# 000018_PGKB_Rev_2_00.net
KiCad netlist of a schematic drawn in EAGLE
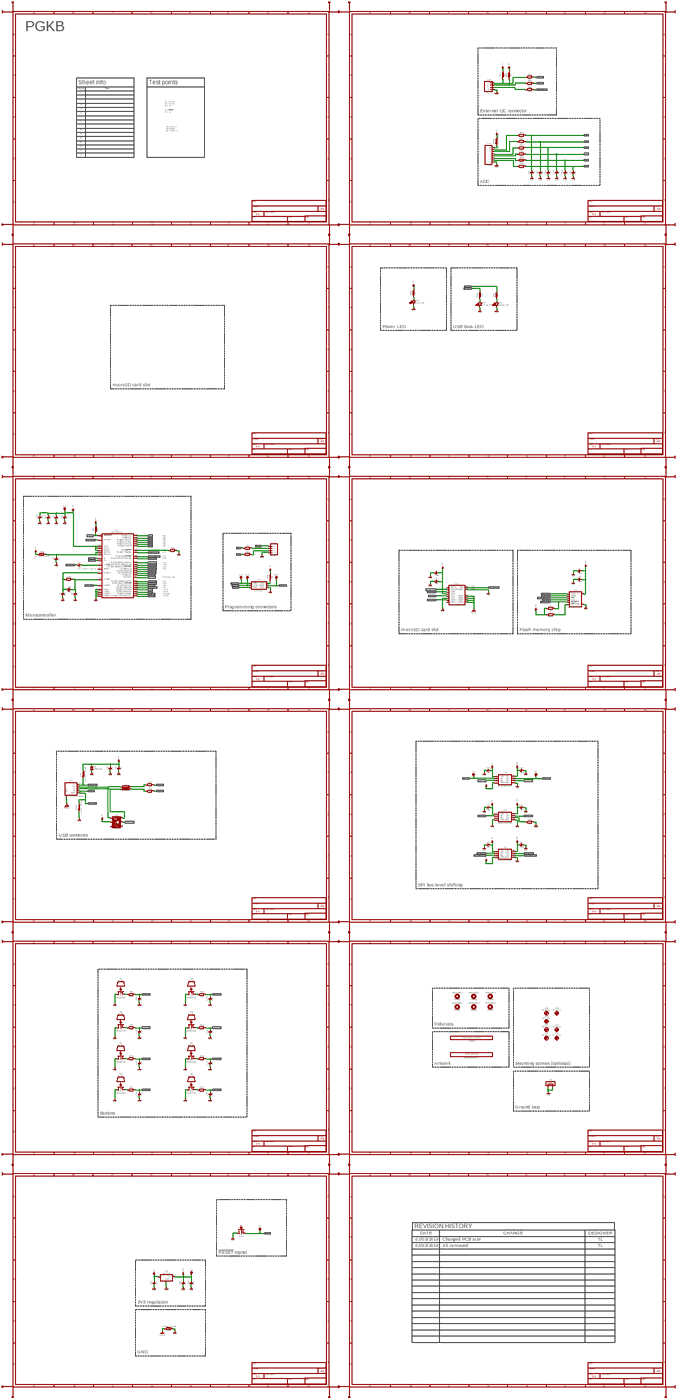
[diagram p0: schematic, sheet 1, overview]
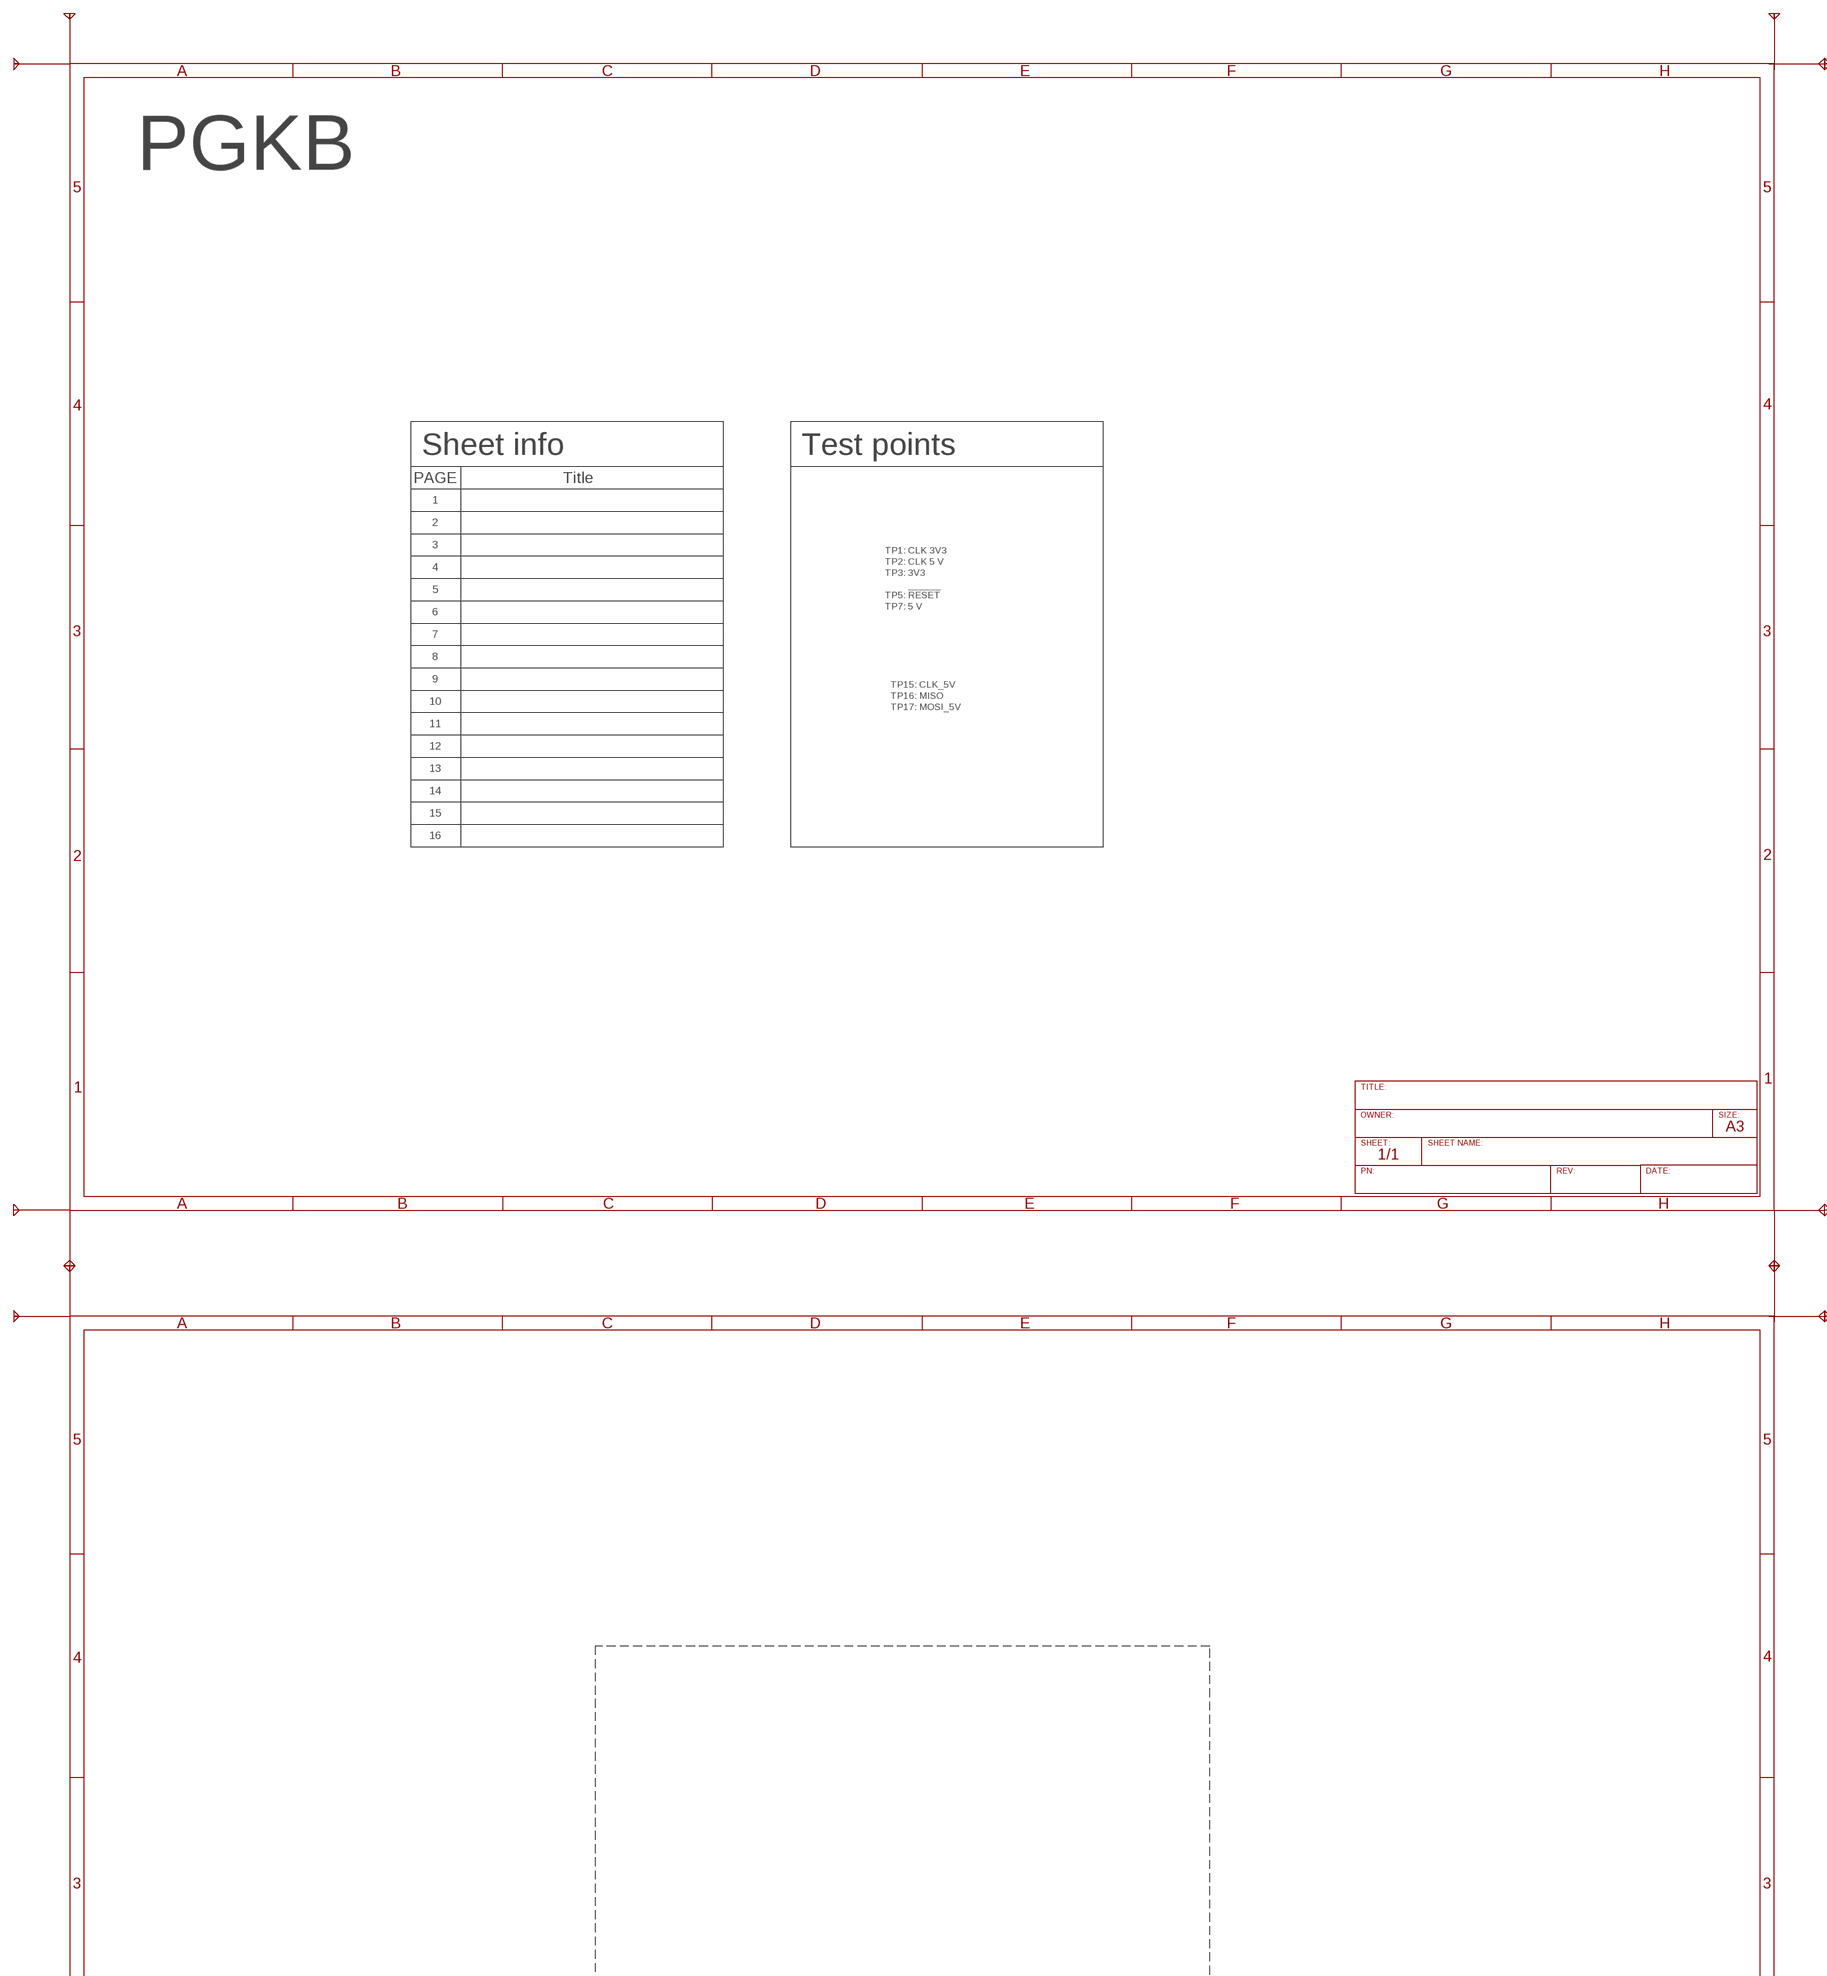
[diagram p1: schematic, sheet 1, part 1 of 8]
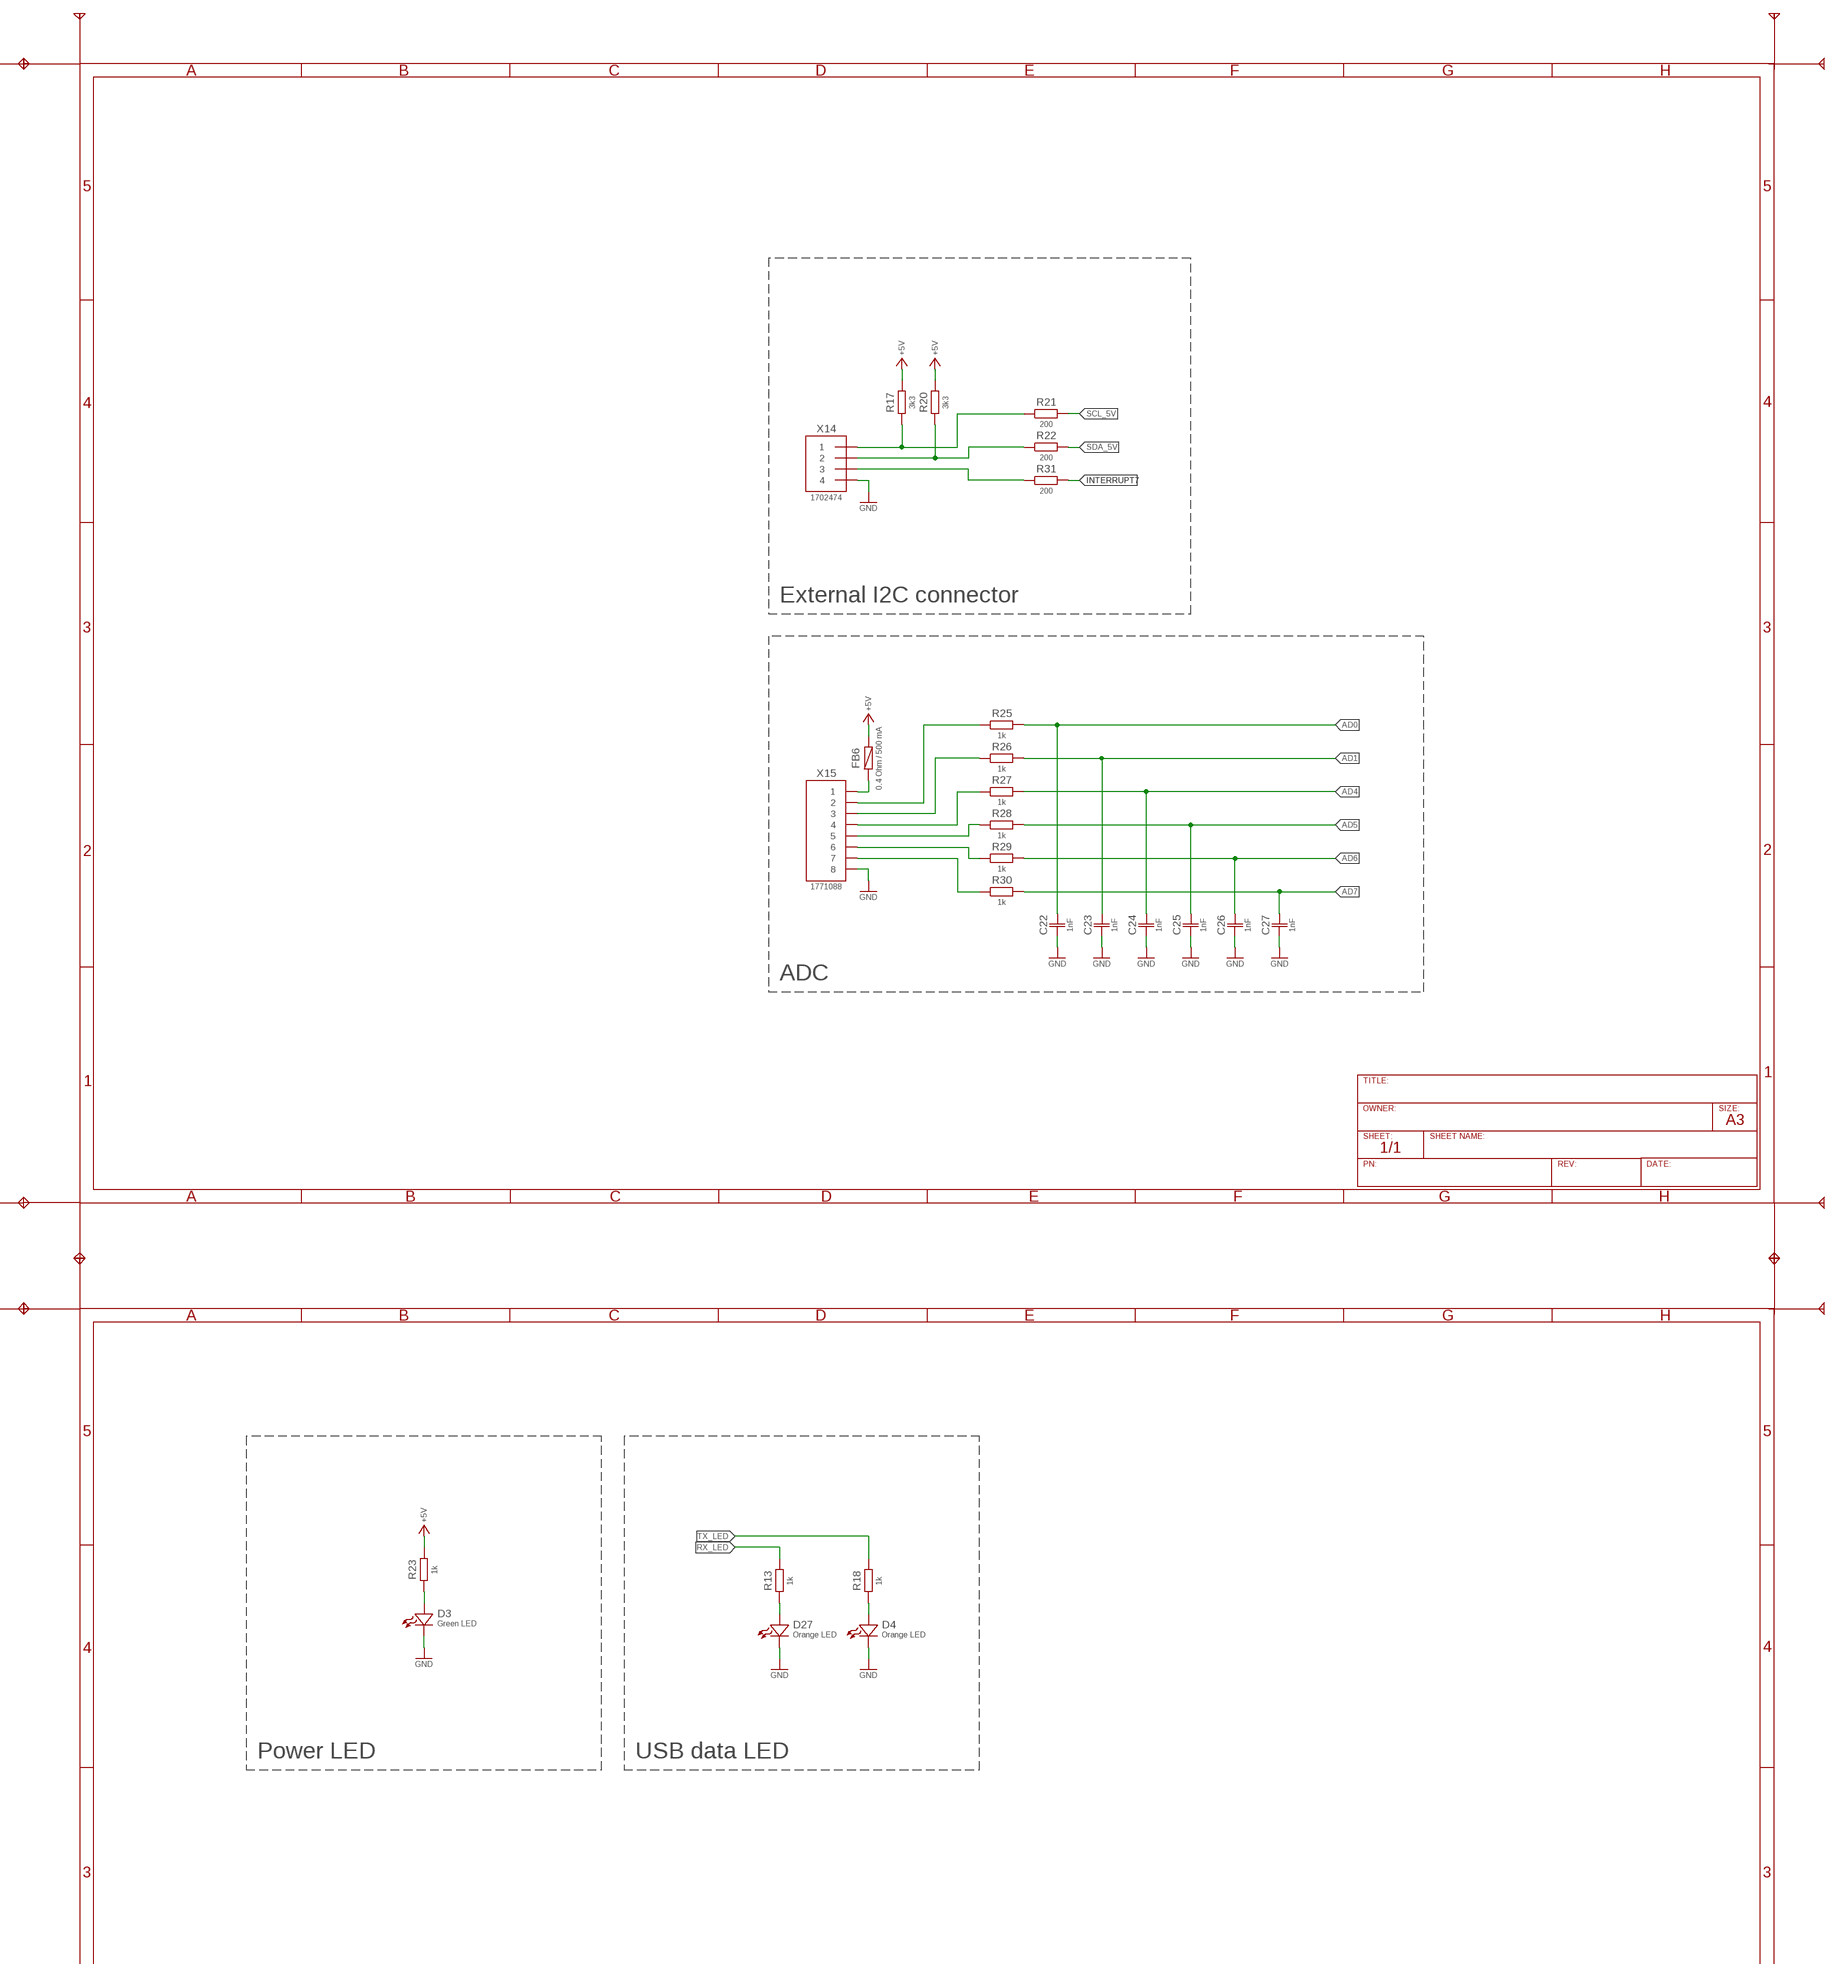
[diagram p2: schematic, sheet 1, part 2 of 8]
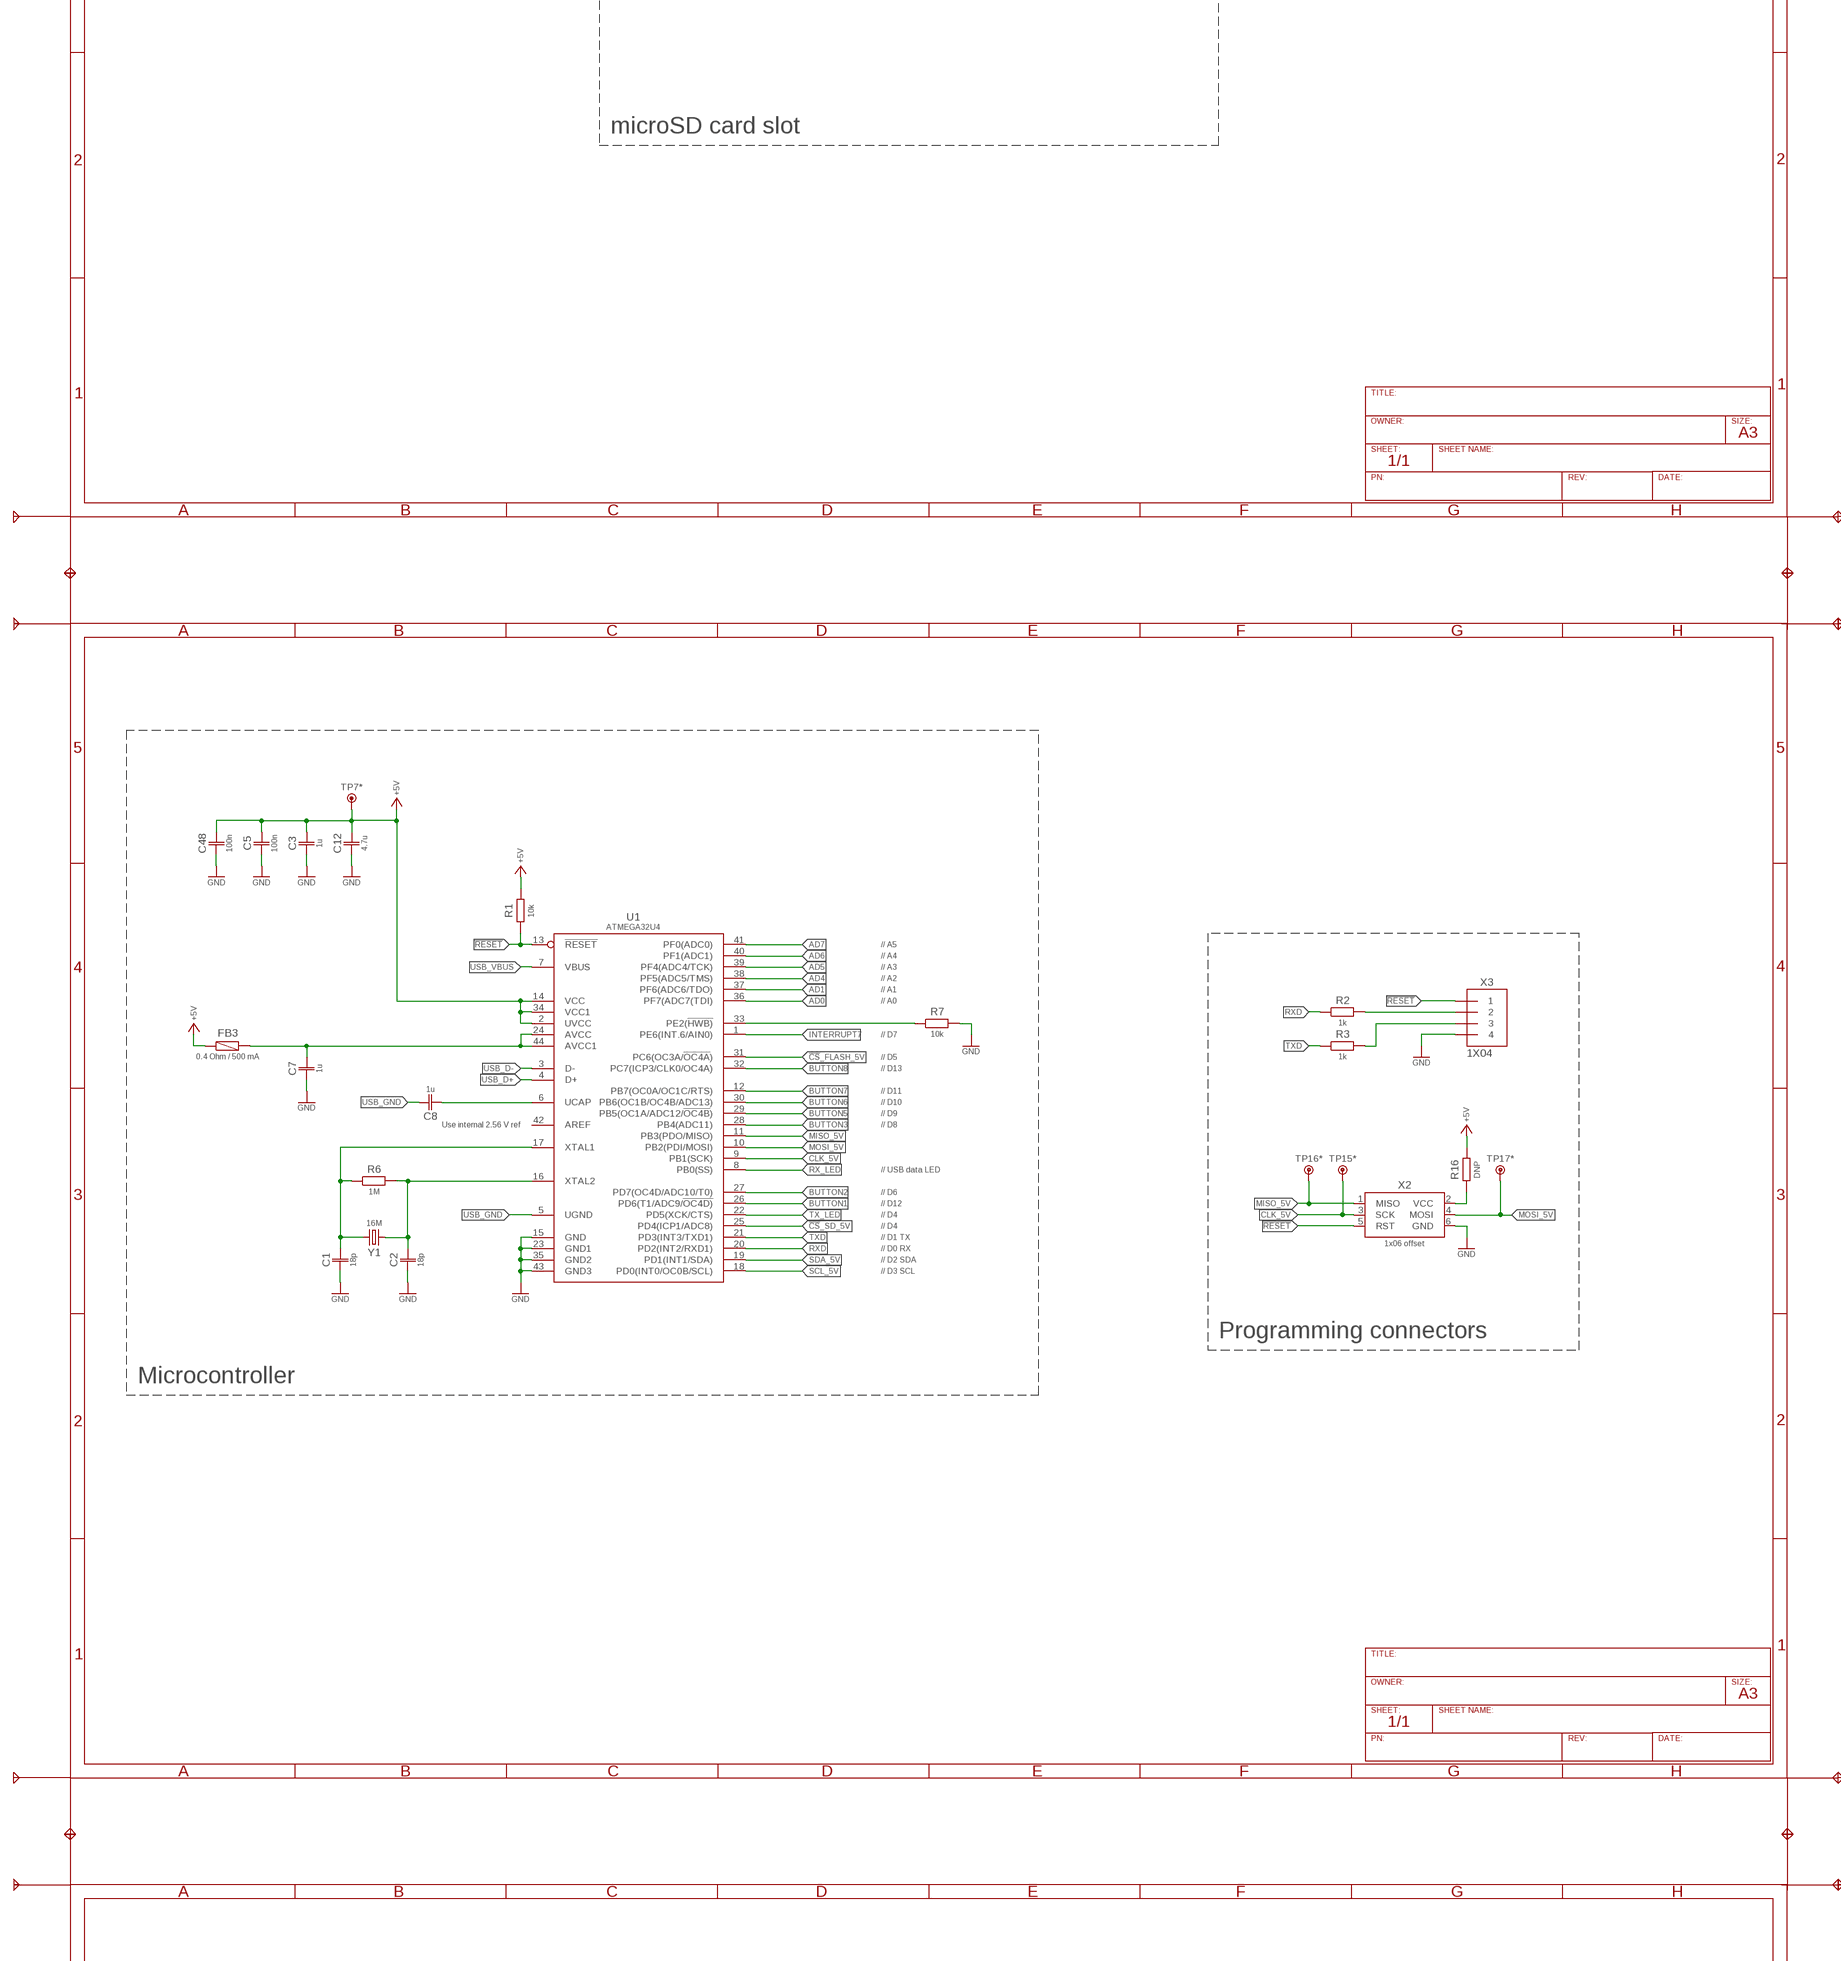
[diagram p3: schematic, sheet 1, part 3 of 8]
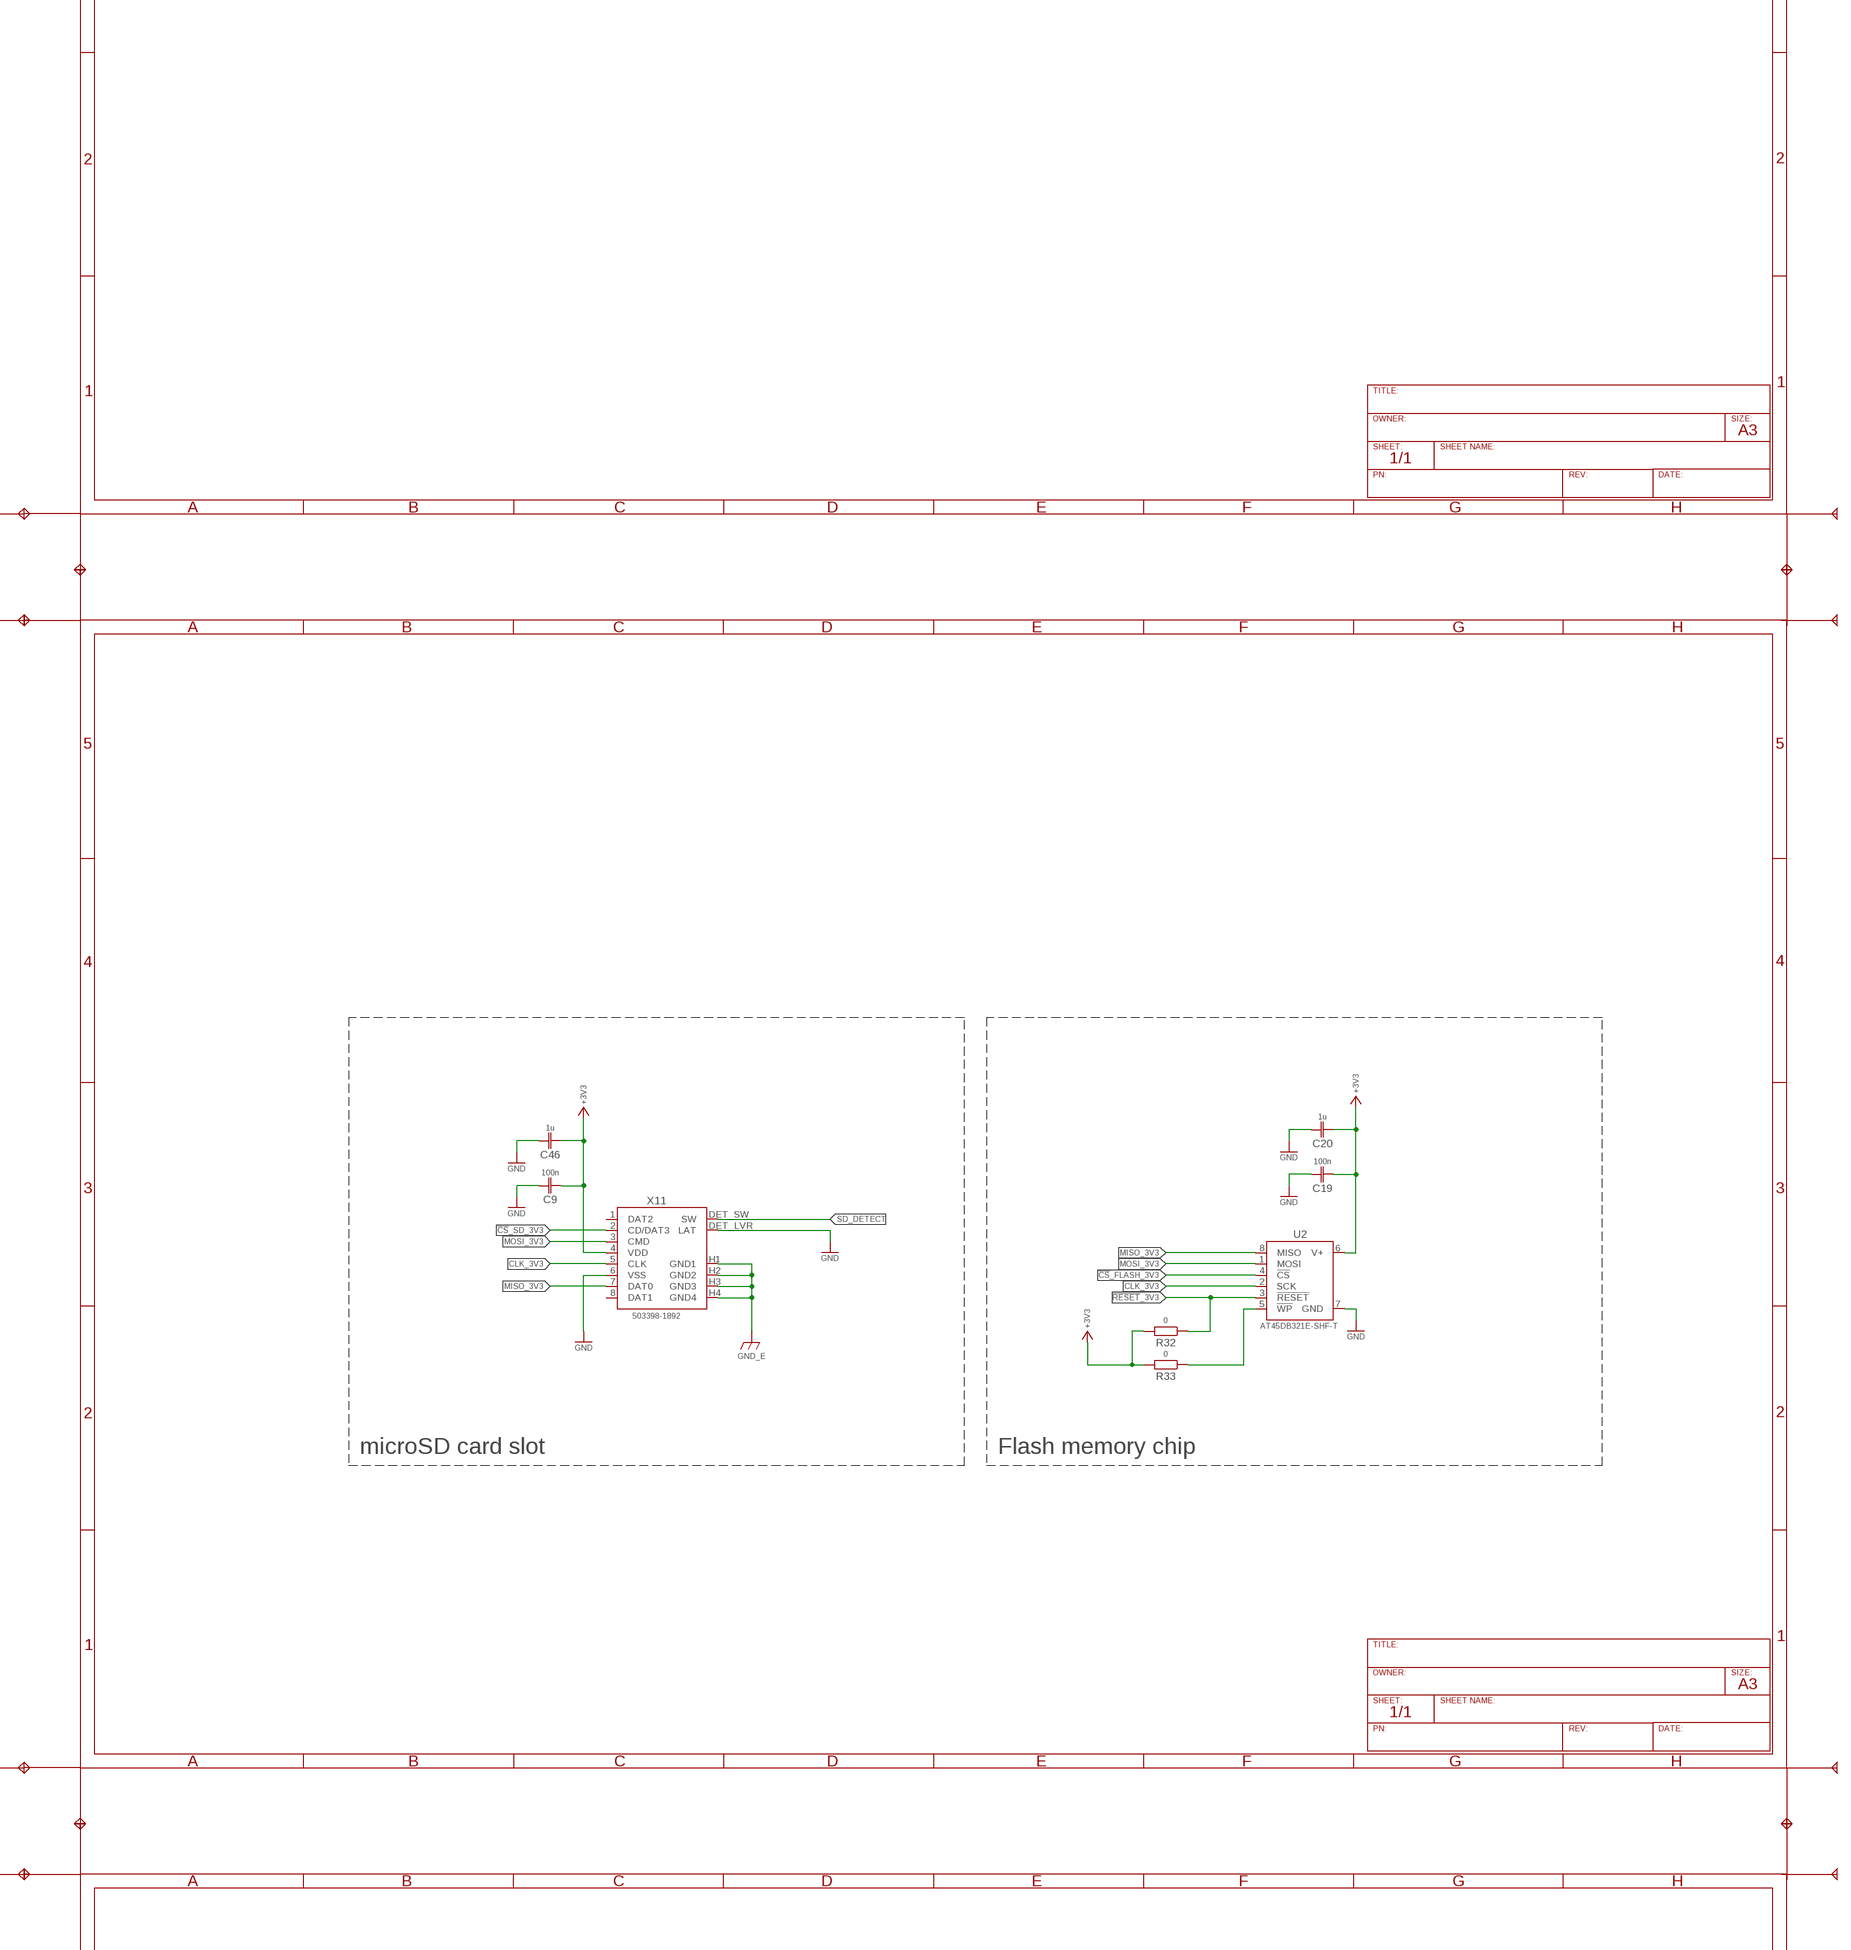
[diagram p4: schematic, sheet 1, part 4 of 8]
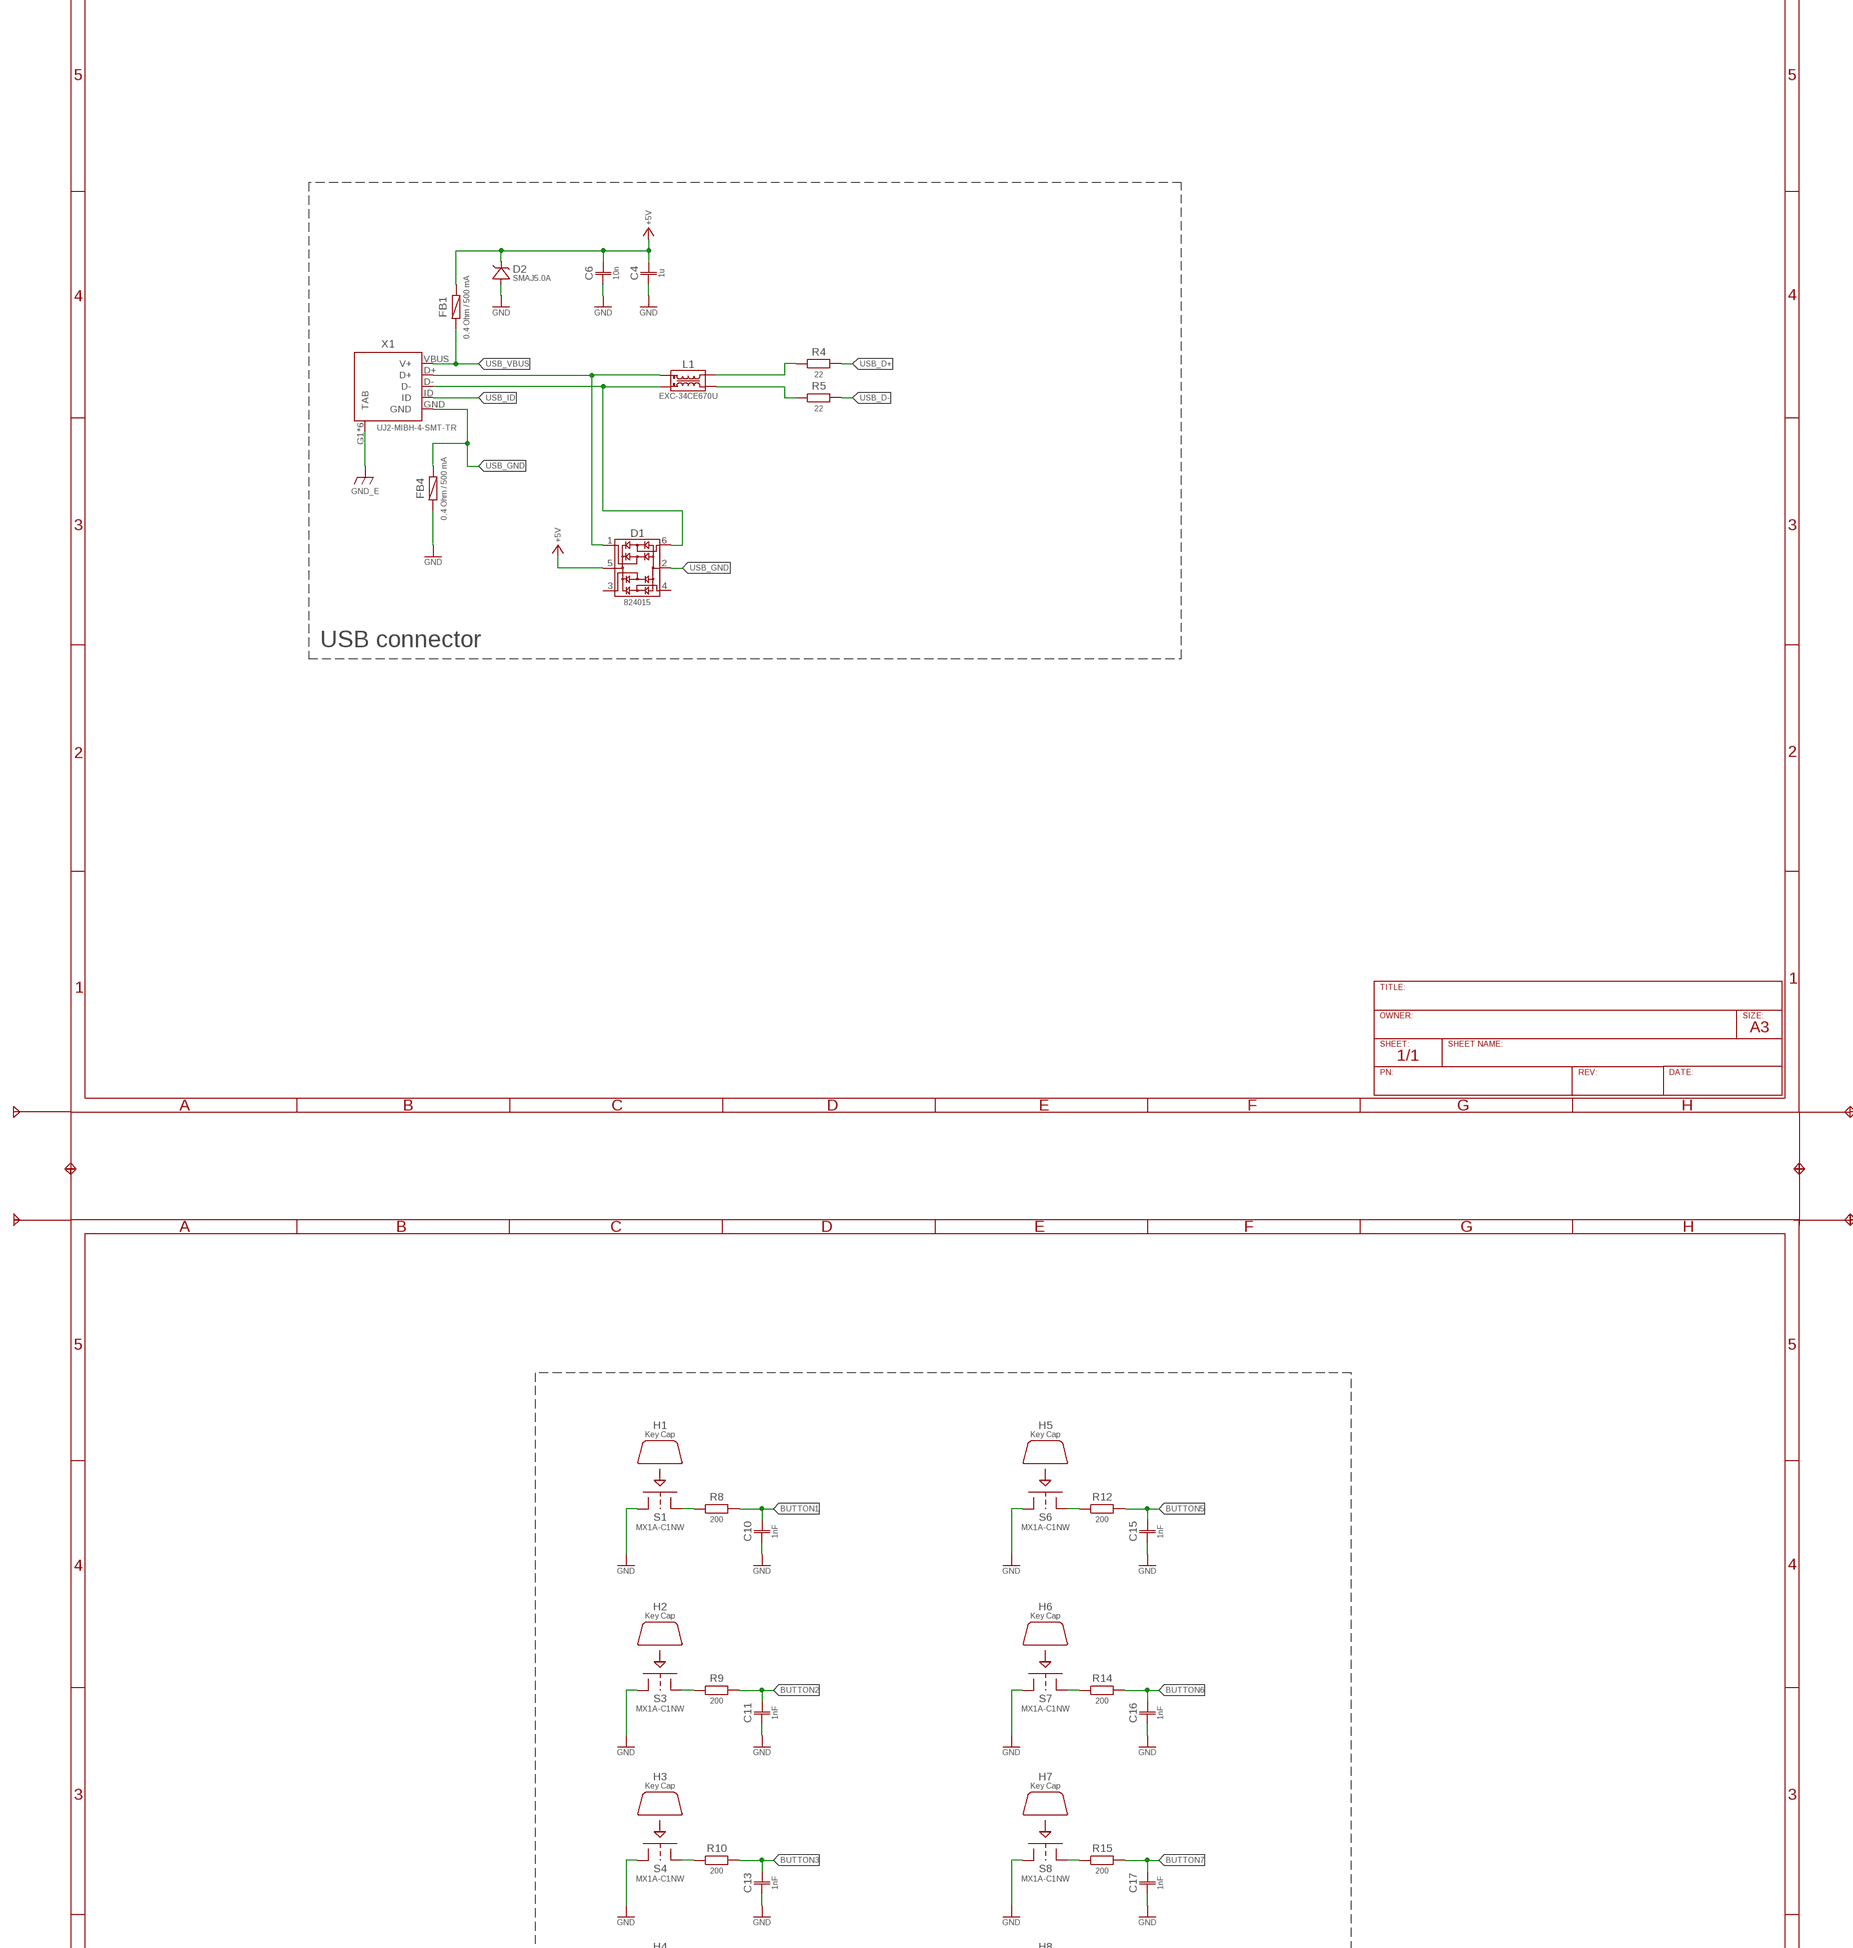
[diagram p5: schematic, sheet 1, part 5 of 8]
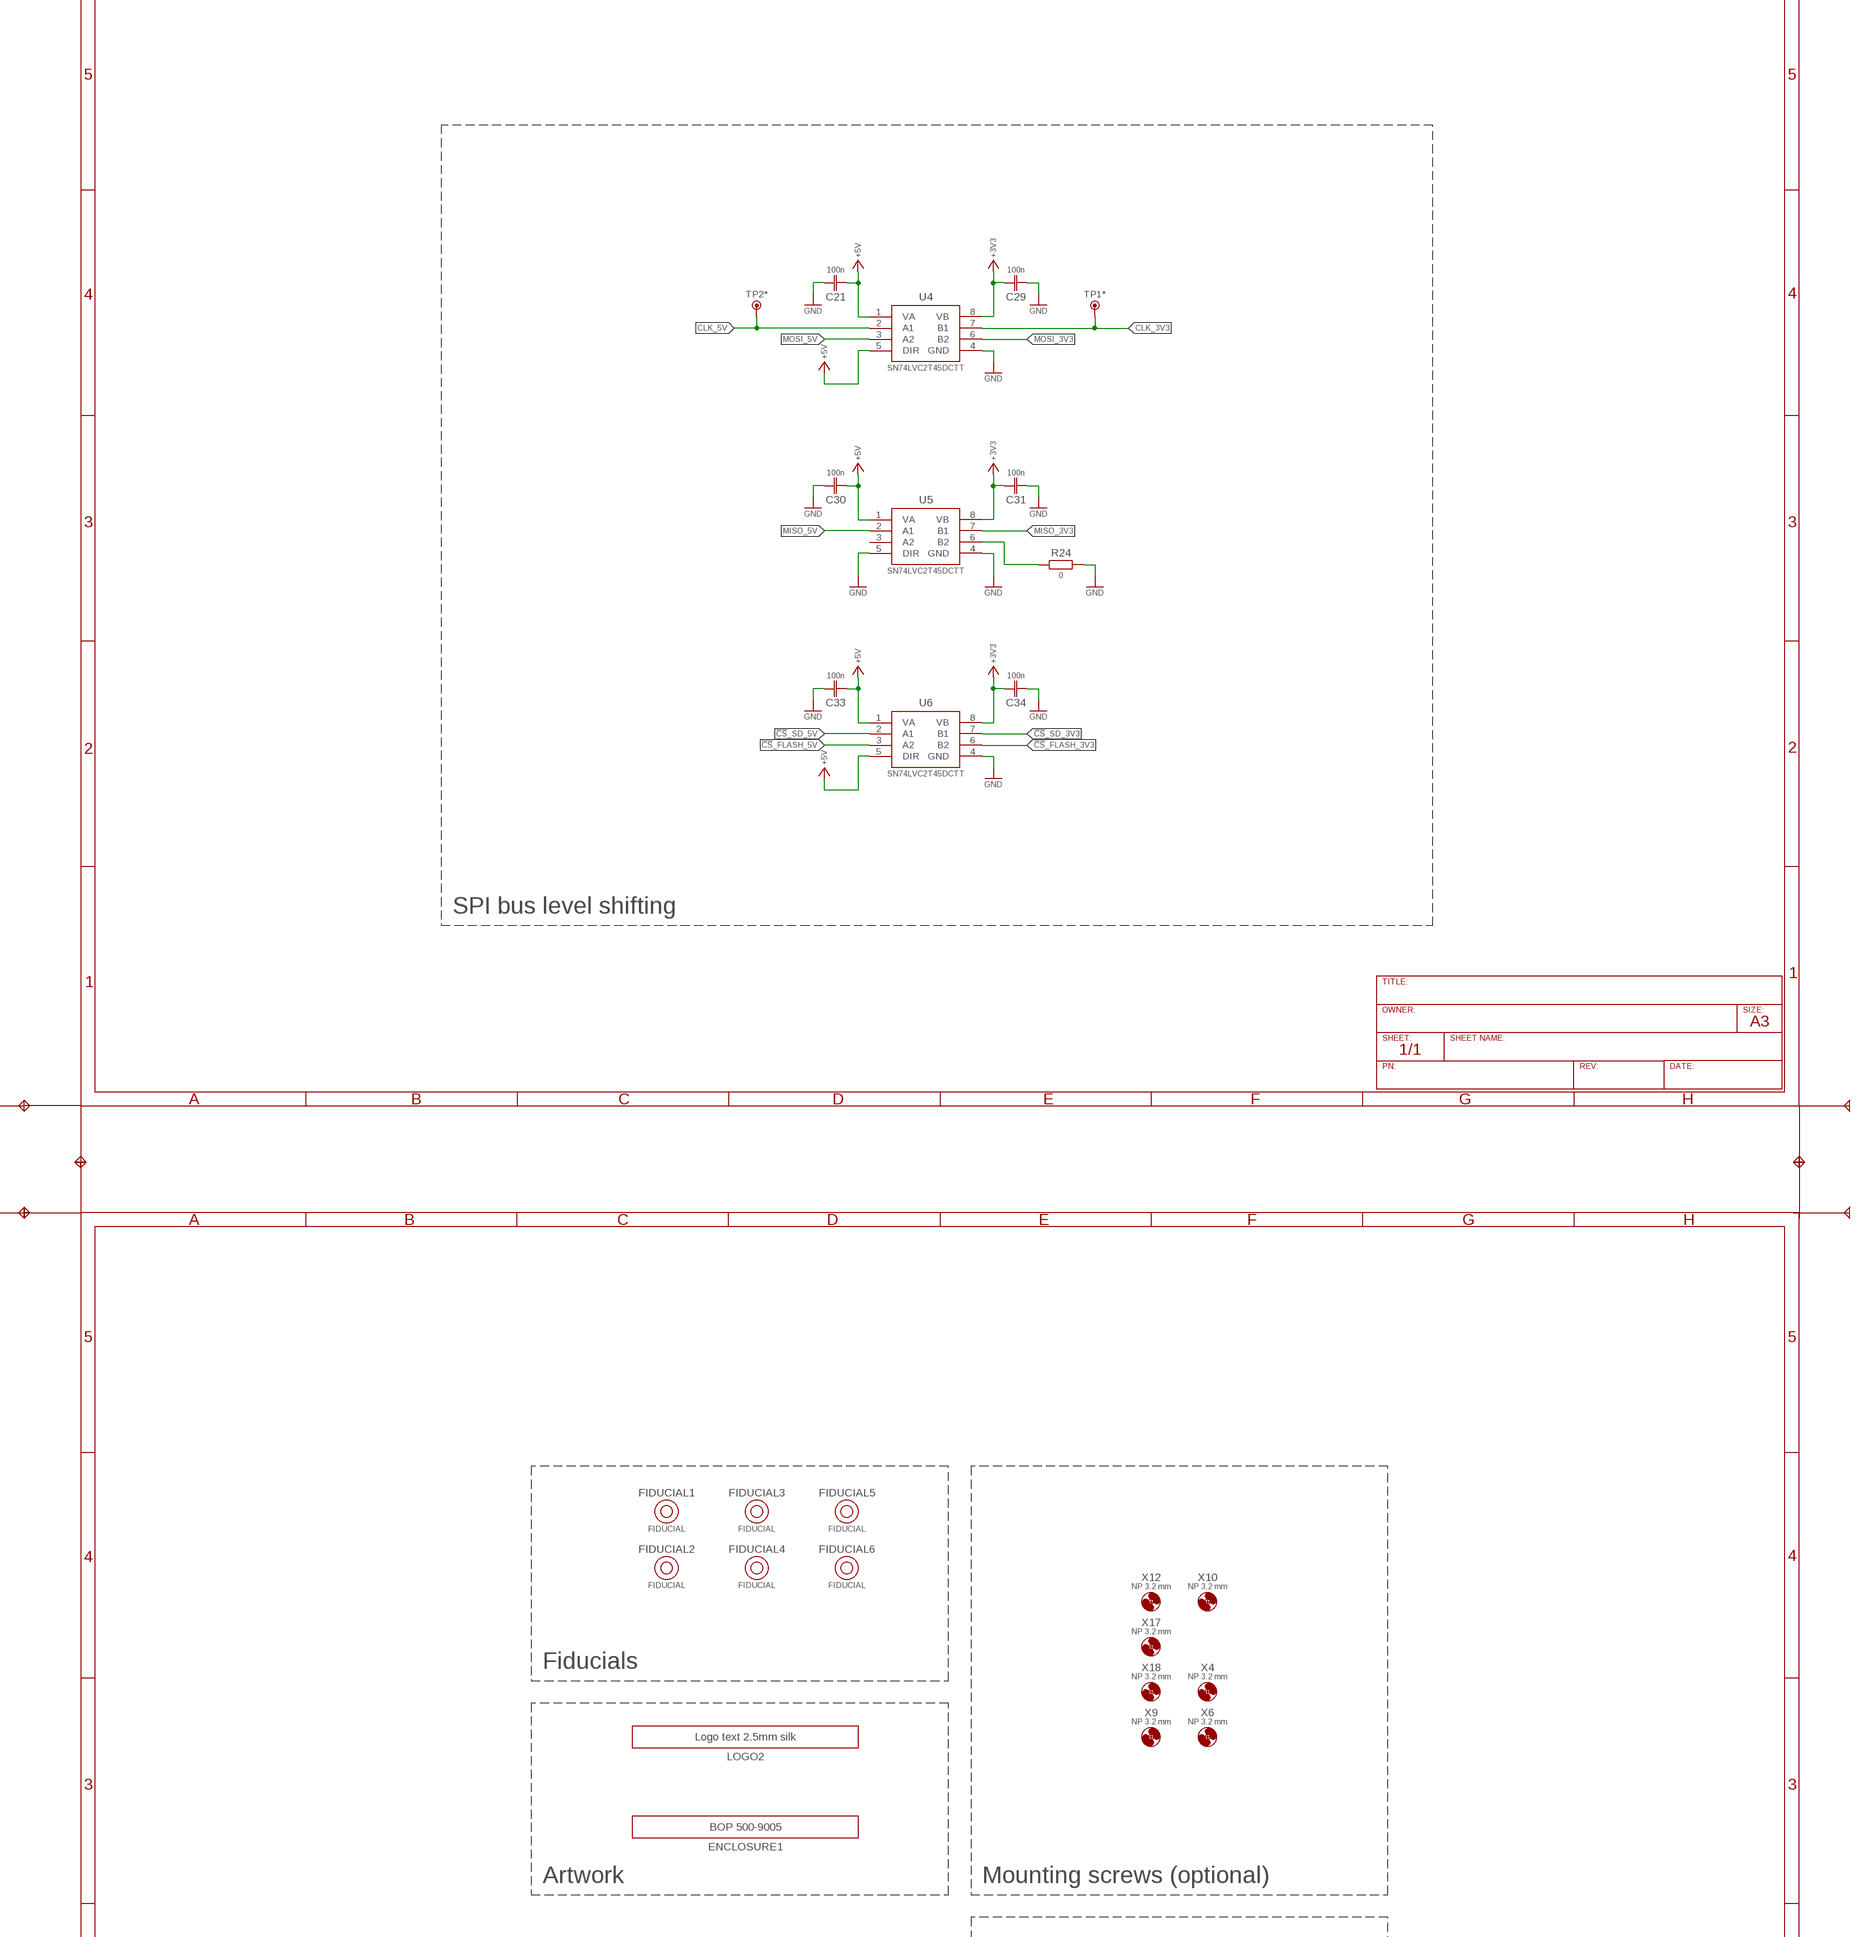
[diagram p6: schematic, sheet 1, part 6 of 8]
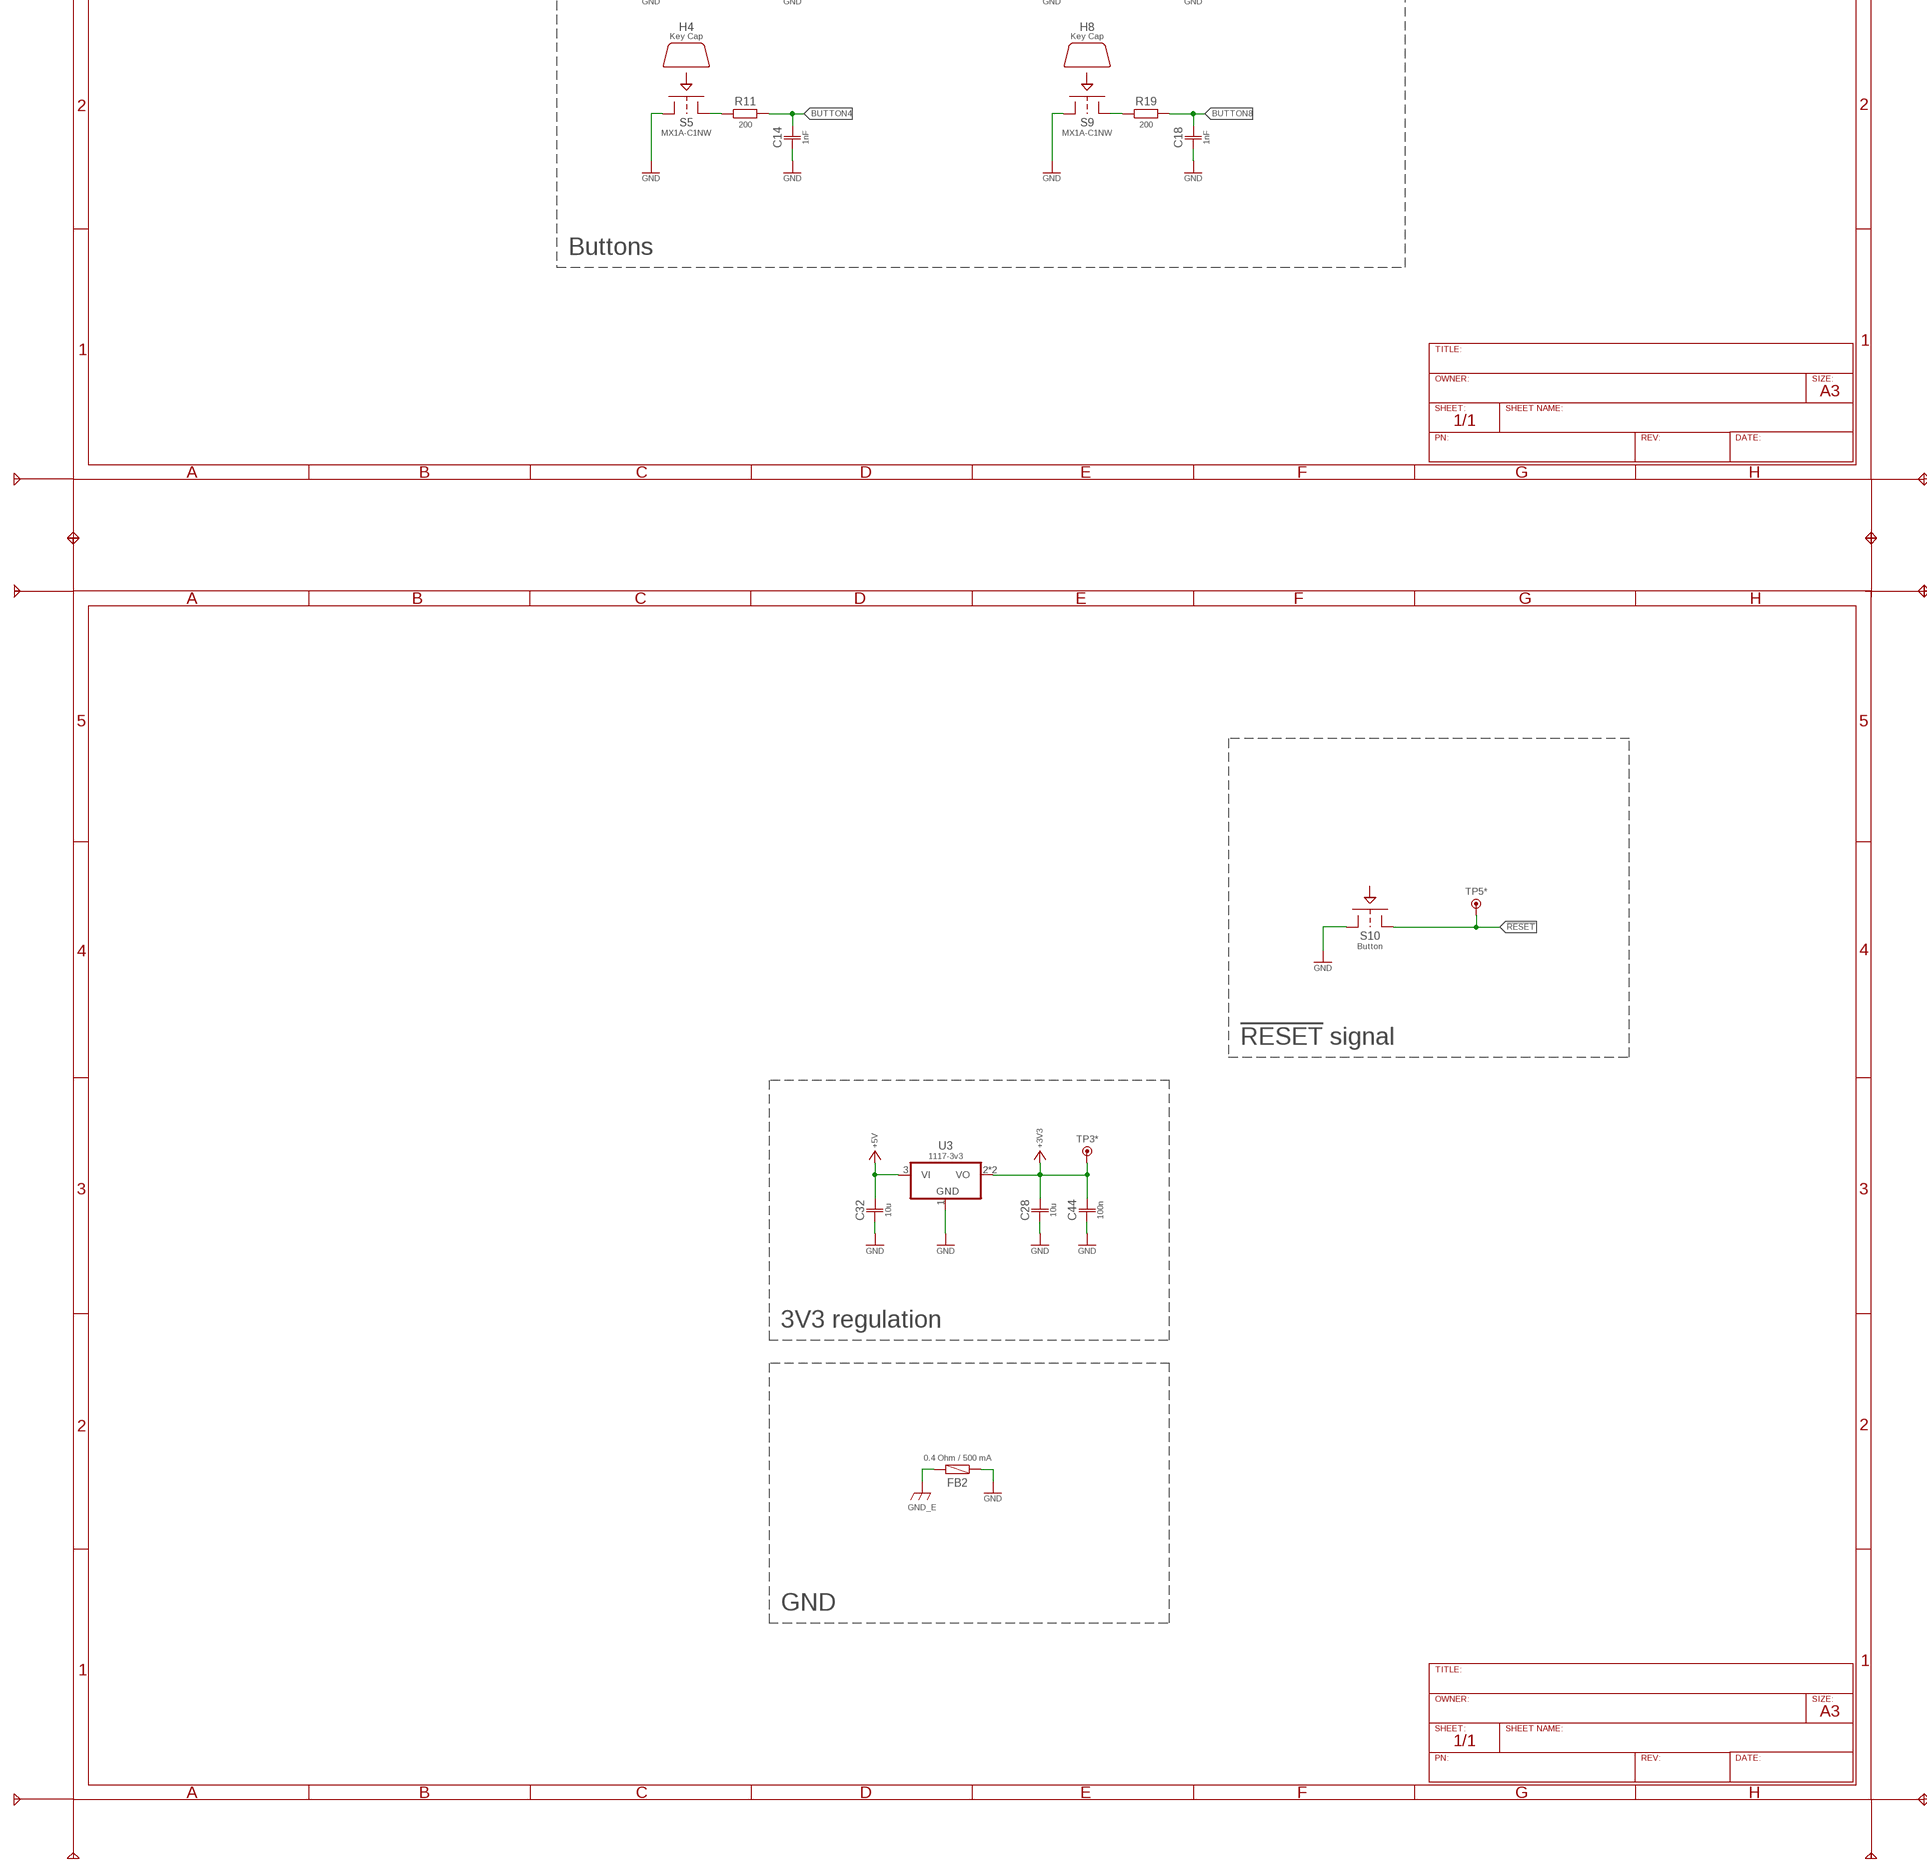
[diagram p7: schematic, sheet 1, part 7 of 8]
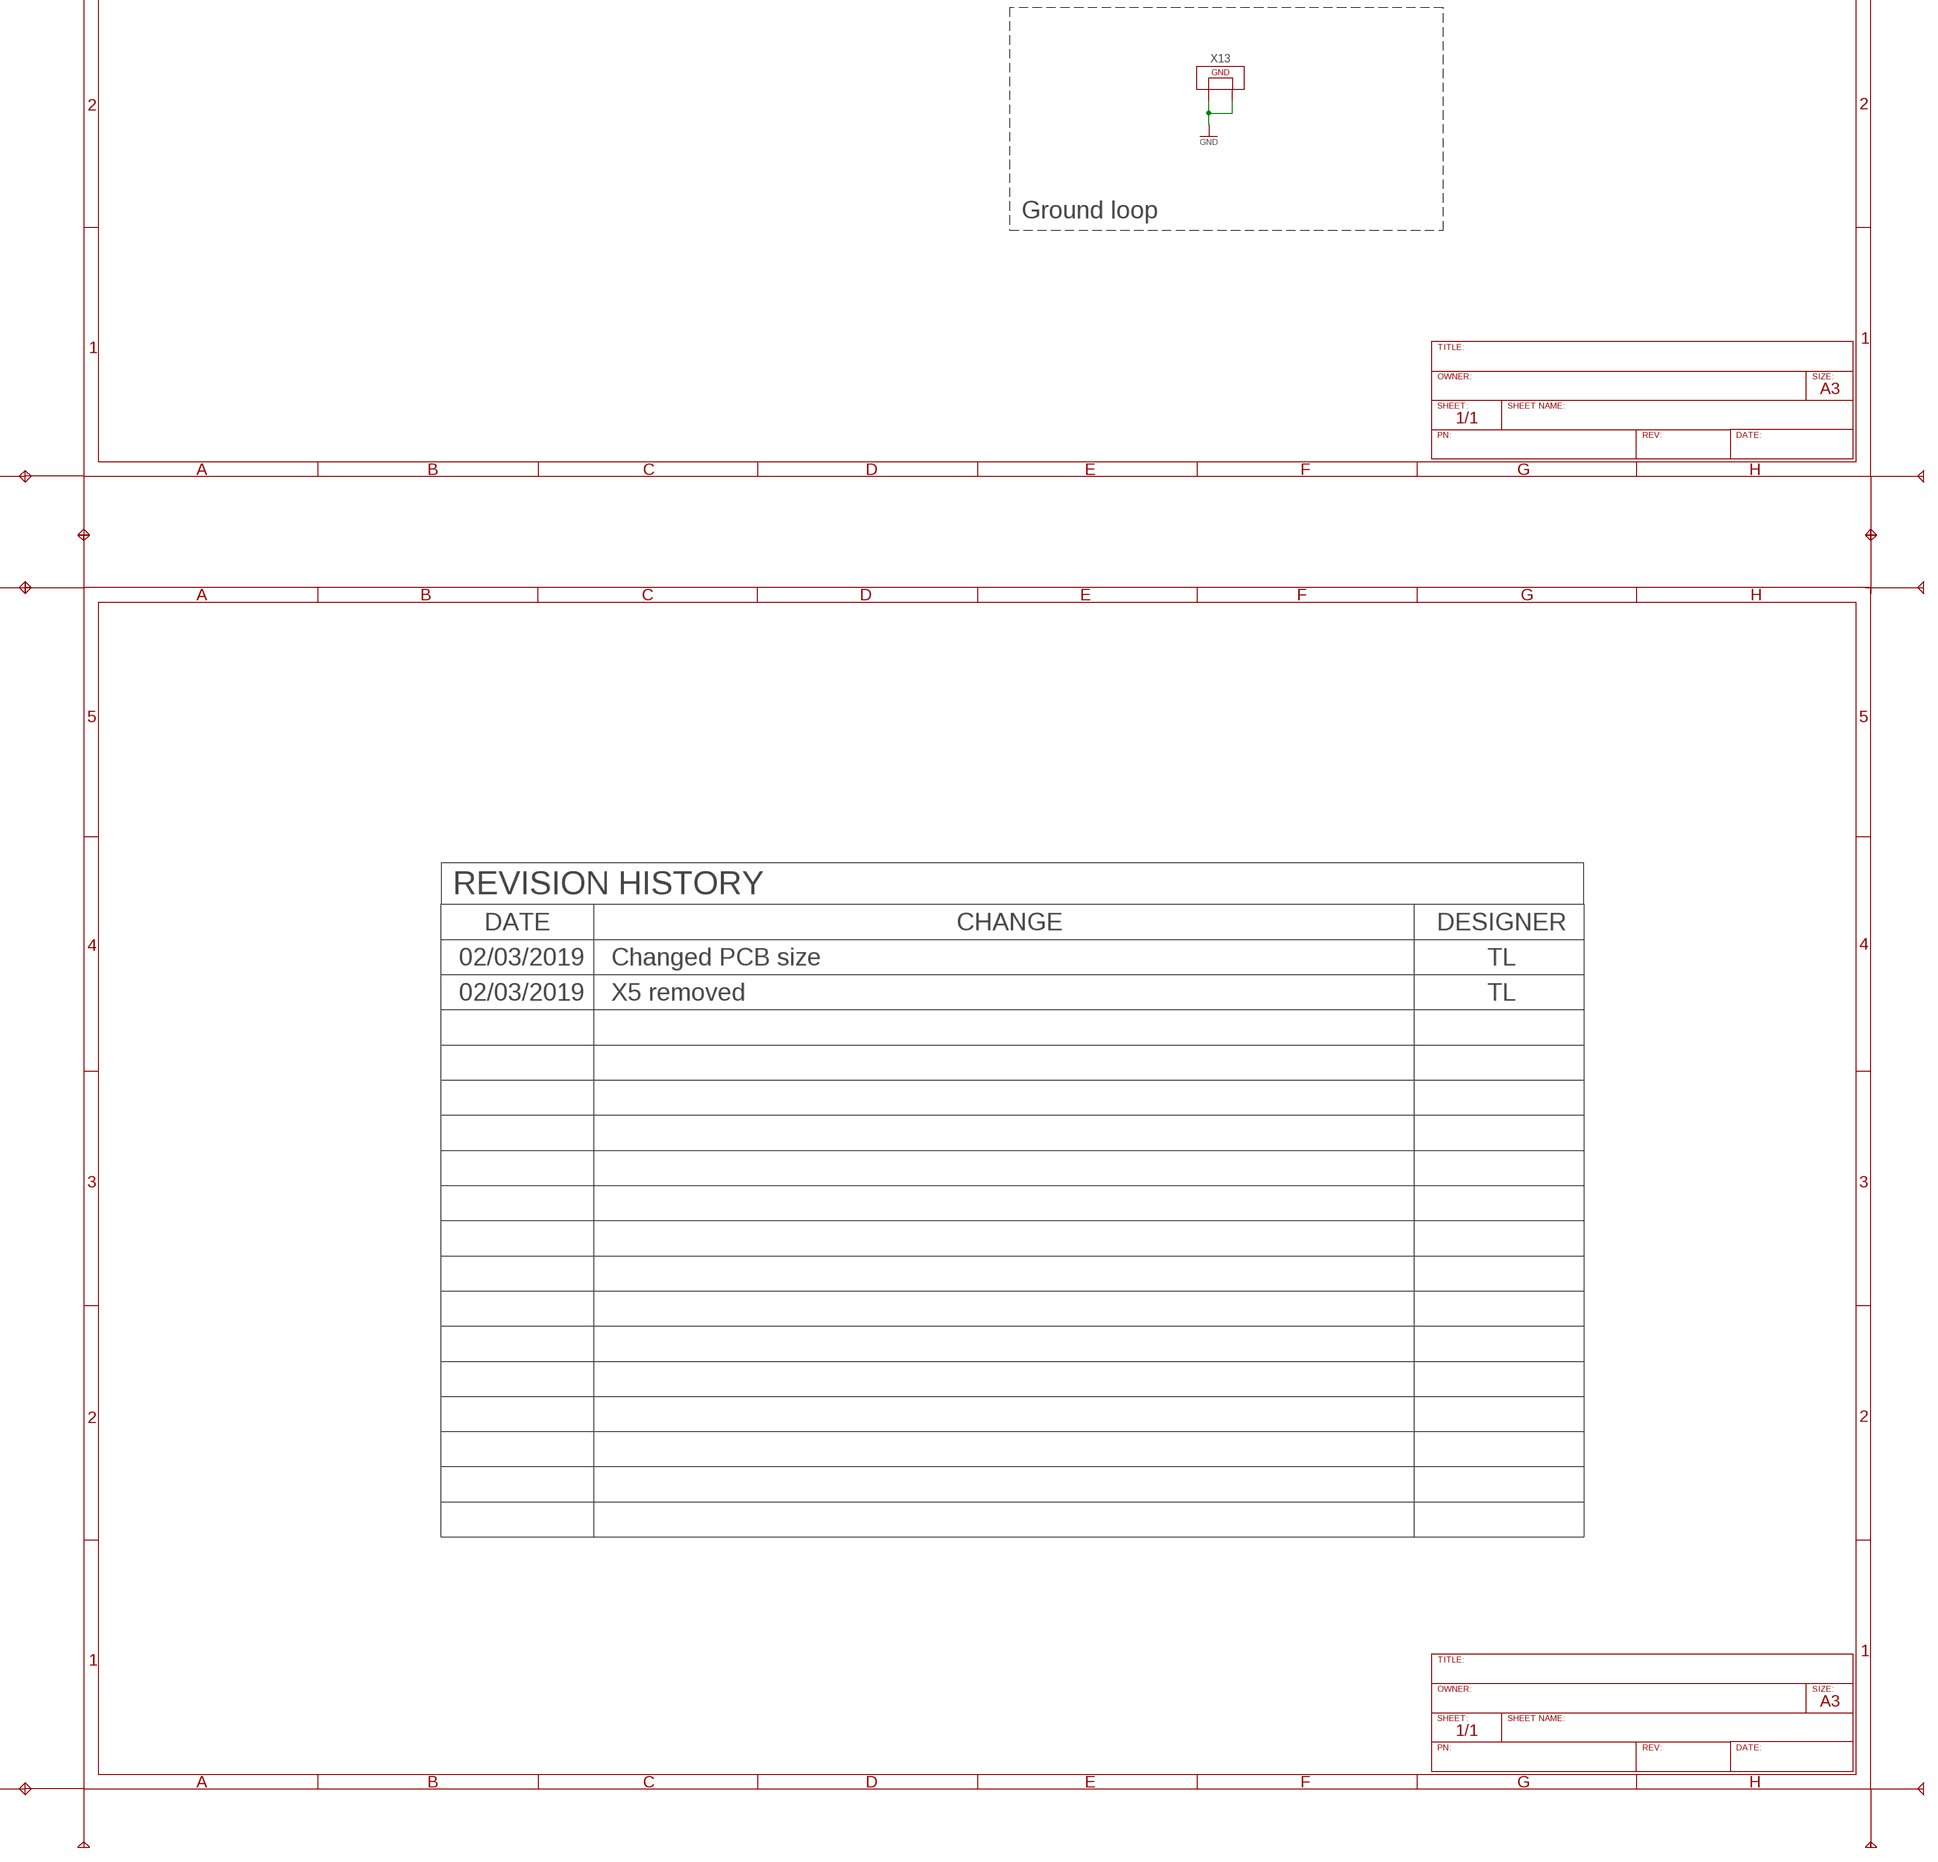
[diagram p8: schematic, sheet 1, part 8 of 8]

(export (version "E")
  (design (tool "Eeschema 10.0.6"))
  (components
    (comp (ref "C1")
      (value "C0805_18PF_50V_NP0")
      (footprint "eagle-import:CAPC2012X160")
      (fields
        (field (name "CODE") "18p")
        (field (name "MANUFACTURER") "Samsung")
        (field (name "MFG_PARTNO") "CL21C180JBANNNC")
      )
      (libsource (lib "eagle-import") (part "C0805_18PF_50V_NP0"))
    )
    (comp (ref "C2")
      (value "C0805_18PF_50V_NP0")
      (footprint "eagle-import:CAPC2012X160")
      (fields
        (field (name "CODE") "18p")
        (field (name "MANUFACTURER") "Samsung")
        (field (name "MFG_PARTNO") "CL21C180JBANNNC")
      )
      (libsource (lib "eagle-import") (part "C0805_18PF_50V_NP0"))
    )
    (comp (ref "C3")
      (value "C0805_1UF_50V_X5R")
      (footprint "eagle-import:CAPC2012X160")
      (fields
        (field (name "CODE") "1u")
        (field (name "MANUFACTURER") "Murata")
        (field (name "MFG_PARTNO") "GRM219R61H105KA73D")
      )
      (libsource (lib "eagle-import") (part "C0805_1UF_50V_X5R"))
    )
    (comp (ref "C4")
      (value "C0805_1UF_50V_X5R")
      (footprint "eagle-import:CAPC2012X160")
      (fields
        (field (name "CODE") "1u")
        (field (name "MANUFACTURER") "Murata")
        (field (name "MFG_PARTNO") "GRM219R61H105KA73D")
      )
      (libsource (lib "eagle-import") (part "C0805_1UF_50V_X5R"))
    )
    (comp (ref "C5")
      (value "C0603_100NF_50V_X7R")
      (footprint "eagle-import:CAPC1608X90")
      (fields
        (field (name "CODE") "100n")
        (field (name "MANUFACTURER") "Samsung")
        (field (name "MFG_PARTNO") "CL10B104MB8NNNC")
      )
      (libsource (lib "eagle-import") (part "C0603_100NF_50V_X7R"))
    )
    (comp (ref "C6")
      (value "C0805_10NF_50V_X7R")
      (footprint "eagle-import:CAPC2012X160")
      (fields
        (field (name "CODE") "10n")
        (field (name "MANUFACTURER") "Samsung")
        (field (name "MFG_PARTNO") "CL21B103KBANNNC")
      )
      (libsource (lib "eagle-import") (part "C0805_10NF_50V_X7R"))
    )
    (comp (ref "C7")
      (value "C0805_1UF_50V_X5R")
      (footprint "eagle-import:CAPC2012X160")
      (fields
        (field (name "CODE") "1u")
        (field (name "MANUFACTURER") "Murata")
        (field (name "MFG_PARTNO") "GRM219R61H105KA73D")
      )
      (libsource (lib "eagle-import") (part "C0805_1UF_50V_X5R"))
    )
    (comp (ref "C8")
      (value "C0805_1UF_50V_X5R")
      (footprint "eagle-import:CAPC2012X160")
      (fields
        (field (name "CODE") "1u")
        (field (name "MANUFACTURER") "Murata")
        (field (name "MFG_PARTNO") "GRM219R61H105KA73D")
      )
      (libsource (lib "eagle-import") (part "C0805_1UF_50V_X5R"))
    )
    (comp (ref "C9")
      (value "C0603_100NF_50V_X7R")
      (footprint "eagle-import:CAPC1608X90")
      (fields
        (field (name "CODE") "100n")
        (field (name "MANUFACTURER") "Samsung")
        (field (name "MFG_PARTNO") "CL10B104MB8NNNC")
      )
      (libsource (lib "eagle-import") (part "C0603_100NF_50V_X7R"))
    )
    (comp (ref "C10")
      (value "C0805_1NF_50V_X7R")
      (footprint "eagle-import:CAPC2012X160")
      (fields
        (field (name "CODE") "1nF")
        (field (name "MANUFACTURER") "Kemet")
        (field (name "MFG_PARTNO") "C0805C102K5RACTU")
      )
      (libsource (lib "eagle-import") (part "C0805_1NF_50V_X7R"))
    )
    (comp (ref "C11")
      (value "C0805_1NF_50V_X7R")
      (footprint "eagle-import:CAPC2012X160")
      (fields
        (field (name "CODE") "1nF")
        (field (name "MANUFACTURER") "Kemet")
        (field (name "MFG_PARTNO") "C0805C102K5RACTU")
      )
      (libsource (lib "eagle-import") (part "C0805_1NF_50V_X7R"))
    )
    (comp (ref "C12")
      (value "C0805_4.7UF_25V_X5R")
      (footprint "eagle-import:CAPC2012X160")
      (fields
        (field (name "CODE") "4.7u")
        (field (name "MANUFACTURER") "Samsung")
        (field (name "MFG_PARTNO") "CL21A475KAQNNNG")
      )
      (libsource (lib "eagle-import") (part "C0805_4.7UF_25V_X5R"))
    )
    (comp (ref "C13")
      (value "C0805_1NF_50V_X7R")
      (footprint "eagle-import:CAPC2012X160")
      (fields
        (field (name "CODE") "1nF")
        (field (name "MANUFACTURER") "Kemet")
        (field (name "MFG_PARTNO") "C0805C102K5RACTU")
      )
      (libsource (lib "eagle-import") (part "C0805_1NF_50V_X7R"))
    )
    (comp (ref "C14")
      (value "C0805_1NF_50V_X7R")
      (footprint "eagle-import:CAPC2012X160")
      (fields
        (field (name "CODE") "1nF")
        (field (name "MANUFACTURER") "Kemet")
        (field (name "MFG_PARTNO") "C0805C102K5RACTU")
      )
      (libsource (lib "eagle-import") (part "C0805_1NF_50V_X7R"))
    )
    (comp (ref "C15")
      (value "C0805_1NF_50V_X7R")
      (footprint "eagle-import:CAPC2012X160")
      (fields
        (field (name "CODE") "1nF")
        (field (name "MANUFACTURER") "Kemet")
        (field (name "MFG_PARTNO") "C0805C102K5RACTU")
      )
      (libsource (lib "eagle-import") (part "C0805_1NF_50V_X7R"))
    )
    (comp (ref "C16")
      (value "C0805_1NF_50V_X7R")
      (footprint "eagle-import:CAPC2012X160")
      (fields
        (field (name "CODE") "1nF")
        (field (name "MANUFACTURER") "Kemet")
        (field (name "MFG_PARTNO") "C0805C102K5RACTU")
      )
      (libsource (lib "eagle-import") (part "C0805_1NF_50V_X7R"))
    )
    (comp (ref "C17")
      (value "C0805_1NF_50V_X7R")
      (footprint "eagle-import:CAPC2012X160")
      (fields
        (field (name "CODE") "1nF")
        (field (name "MANUFACTURER") "Kemet")
        (field (name "MFG_PARTNO") "C0805C102K5RACTU")
      )
      (libsource (lib "eagle-import") (part "C0805_1NF_50V_X7R"))
    )
    (comp (ref "C18")
      (value "C0805_1NF_50V_X7R")
      (footprint "eagle-import:CAPC2012X160")
      (fields
        (field (name "CODE") "1nF")
        (field (name "MANUFACTURER") "Kemet")
        (field (name "MFG_PARTNO") "C0805C102K5RACTU")
      )
      (libsource (lib "eagle-import") (part "C0805_1NF_50V_X7R"))
    )
    (comp (ref "C19")
      (value "C0603_100NF_50V_X7R")
      (footprint "eagle-import:CAPC1608X90")
      (fields
        (field (name "CODE") "100n")
        (field (name "MANUFACTURER") "Samsung")
        (field (name "MFG_PARTNO") "CL10B104MB8NNNC")
      )
      (libsource (lib "eagle-import") (part "C0603_100NF_50V_X7R"))
    )
    (comp (ref "C20")
      (value "C0805_1UF_50V_X5R")
      (footprint "eagle-import:CAPC2012X160")
      (fields
        (field (name "CODE") "1u")
        (field (name "MANUFACTURER") "Murata")
        (field (name "MFG_PARTNO") "GRM219R61H105KA73D")
      )
      (libsource (lib "eagle-import") (part "C0805_1UF_50V_X5R"))
    )
    (comp (ref "C21")
      (value "C0603_100NF_50V_X7R")
      (footprint "eagle-import:CAPC1608X90")
      (fields
        (field (name "CODE") "100n")
        (field (name "MANUFACTURER") "Samsung")
        (field (name "MFG_PARTNO") "CL10B104MB8NNNC")
      )
      (libsource (lib "eagle-import") (part "C0603_100NF_50V_X7R"))
    )
    (comp (ref "C22")
      (value "C0805_1NF_50V_X7R")
      (footprint "eagle-import:CAPC2012X160")
      (fields
        (field (name "CODE") "1nF")
        (field (name "MANUFACTURER") "Kemet")
        (field (name "MFG_PARTNO") "C0805C102K5RACTU")
      )
      (libsource (lib "eagle-import") (part "C0805_1NF_50V_X7R"))
    )
    (comp (ref "C23")
      (value "C0805_1NF_50V_X7R")
      (footprint "eagle-import:CAPC2012X160")
      (fields
        (field (name "CODE") "1nF")
        (field (name "MANUFACTURER") "Kemet")
        (field (name "MFG_PARTNO") "C0805C102K5RACTU")
      )
      (libsource (lib "eagle-import") (part "C0805_1NF_50V_X7R"))
    )
    (comp (ref "C24")
      (value "C0805_1NF_50V_X7R")
      (footprint "eagle-import:CAPC2012X160")
      (fields
        (field (name "CODE") "1nF")
        (field (name "MANUFACTURER") "Kemet")
        (field (name "MFG_PARTNO") "C0805C102K5RACTU")
      )
      (libsource (lib "eagle-import") (part "C0805_1NF_50V_X7R"))
    )
    (comp (ref "C25")
      (value "C0805_1NF_50V_X7R")
      (footprint "eagle-import:CAPC2012X160")
      (fields
        (field (name "CODE") "1nF")
        (field (name "MANUFACTURER") "Kemet")
        (field (name "MFG_PARTNO") "C0805C102K5RACTU")
      )
      (libsource (lib "eagle-import") (part "C0805_1NF_50V_X7R"))
    )
    (comp (ref "C26")
      (value "C0805_1NF_50V_X7R")
      (footprint "eagle-import:CAPC2012X160")
      (fields
        (field (name "CODE") "1nF")
        (field (name "MANUFACTURER") "Kemet")
        (field (name "MFG_PARTNO") "C0805C102K5RACTU")
      )
      (libsource (lib "eagle-import") (part "C0805_1NF_50V_X7R"))
    )
    (comp (ref "C27")
      (value "C0805_1NF_50V_X7R")
      (footprint "eagle-import:CAPC2012X160")
      (fields
        (field (name "CODE") "1nF")
        (field (name "MANUFACTURER") "Kemet")
        (field (name "MFG_PARTNO") "C0805C102K5RACTU")
      )
      (libsource (lib "eagle-import") (part "C0805_1NF_50V_X7R"))
    )
    (comp (ref "C28")
      (value "C1206_10UF_16V_Y5V")
      (footprint "eagle-import:CAPC3216X200")
      (fields
        (field (name "CODE") "10u")
        (field (name "MANUFACTURER") "Yageo")
        (field (name "MFG_PARTNO") "CC1206ZKY5V7BB106")
      )
      (libsource (lib "eagle-import") (part "C1206_10UF_16V_Y5V"))
    )
    (comp (ref "C29")
      (value "C0603_100NF_50V_X7R")
      (footprint "eagle-import:CAPC1608X90")
      (fields
        (field (name "CODE") "100n")
        (field (name "MANUFACTURER") "Samsung")
        (field (name "MFG_PARTNO") "CL10B104MB8NNNC")
      )
      (libsource (lib "eagle-import") (part "C0603_100NF_50V_X7R"))
    )
    (comp (ref "C30")
      (value "C0603_100NF_50V_X7R")
      (footprint "eagle-import:CAPC1608X90")
      (fields
        (field (name "CODE") "100n")
        (field (name "MANUFACTURER") "Samsung")
        (field (name "MFG_PARTNO") "CL10B104MB8NNNC")
      )
      (libsource (lib "eagle-import") (part "C0603_100NF_50V_X7R"))
    )
    (comp (ref "C31")
      (value "C0603_100NF_50V_X7R")
      (footprint "eagle-import:CAPC1608X90")
      (fields
        (field (name "CODE") "100n")
        (field (name "MANUFACTURER") "Samsung")
        (field (name "MFG_PARTNO") "CL10B104MB8NNNC")
      )
      (libsource (lib "eagle-import") (part "C0603_100NF_50V_X7R"))
    )
    (comp (ref "C32")
      (value "C1206_10UF_16V_Y5V")
      (footprint "eagle-import:CAPC3216X200")
      (fields
        (field (name "CODE") "10u")
        (field (name "MANUFACTURER") "Yageo")
        (field (name "MFG_PARTNO") "CC1206ZKY5V7BB106")
      )
      (libsource (lib "eagle-import") (part "C1206_10UF_16V_Y5V"))
    )
    (comp (ref "C33")
      (value "C0603_100NF_50V_X7R")
      (footprint "eagle-import:CAPC1608X90")
      (fields
        (field (name "CODE") "100n")
        (field (name "MANUFACTURER") "Samsung")
        (field (name "MFG_PARTNO") "CL10B104MB8NNNC")
      )
      (libsource (lib "eagle-import") (part "C0603_100NF_50V_X7R"))
    )
    (comp (ref "C34")
      (value "C0603_100NF_50V_X7R")
      (footprint "eagle-import:CAPC1608X90")
      (fields
        (field (name "CODE") "100n")
        (field (name "MANUFACTURER") "Samsung")
        (field (name "MFG_PARTNO") "CL10B104MB8NNNC")
      )
      (libsource (lib "eagle-import") (part "C0603_100NF_50V_X7R"))
    )
    (comp (ref "C44")
      (value "C0603_100NF_50V_X7R")
      (footprint "eagle-import:CAPC1608X90")
      (fields
        (field (name "CODE") "100n")
        (field (name "MANUFACTURER") "Samsung")
        (field (name "MFG_PARTNO") "CL10B104MB8NNNC")
      )
      (libsource (lib "eagle-import") (part "C0603_100NF_50V_X7R"))
    )
    (comp (ref "C46")
      (value "C0805_1UF_50V_X5R")
      (footprint "eagle-import:CAPC2012X160")
      (fields
        (field (name "CODE") "1u")
        (field (name "MANUFACTURER") "Murata")
        (field (name "MFG_PARTNO") "GRM219R61H105KA73D")
      )
      (libsource (lib "eagle-import") (part "C0805_1UF_50V_X5R"))
    )
    (comp (ref "C48")
      (value "C0603_100NF_50V_X7R")
      (footprint "eagle-import:CAPC1608X90")
      (fields
        (field (name "CODE") "100n")
        (field (name "MANUFACTURER") "Samsung")
        (field (name "MFG_PARTNO") "CL10B104MB8NNNC")
      )
      (libsource (lib "eagle-import") (part "C0603_100NF_50V_X7R"))
    )
    (comp (ref "D1")
      (value "DIODE_TVS_5V_BI_824015")
      (footprint "eagle-import:SOP95P280X120-6N")
      (fields
        (field (name "CODE") "824015")
        (field (name "MANUFACTURER") "Wurth")
        (field (name "MFG_PARTNO") "824015")
      )
      (libsource (lib "eagle-import") (part "DIODE_TVS_5V_BI_824015"))
    )
    (comp (ref "D2")
      (value "DIODE_TVS_5V_SMAJ5.0A")
      (footprint "eagle-import:DIOC530X280X230_SMA_A")
      (fields
        (field (name "CODE") "SMAJ5.0A")
        (field (name "MANUFACTURER") "Vishay Semiconductor Diodes Division")
        (field (name "MFG_PARTNO") "SMAJ5.0A-E3/61")
      )
      (libsource (lib "eagle-import") (part "DIODE_TVS_5V_SMAJ5.0A"))
    )
    (comp (ref "D3")
      (value "LED_0603_GREEN_CLEAR_APTD1608CGCK")
      (footprint "eagle-import:LEDM1608X80N_DOME")
      (fields
        (field (name "CODE") "Green LED")
        (field (name "MANUFACTURER") "Kingbright")
        (field (name "MFG_PARTNO") "APTD1608CGCK")
      )
      (libsource (lib "eagle-import") (part "LED_0603_GREEN_CLEAR_APTD1608CGCK"))
    )
    (comp (ref "D4")
      (value "LED_0603_AMBER_DIFF_LOQ976-PS-25")
      (footprint "eagle-import:LEDM1608X80N")
      (fields
        (field (name "CODE") "Orange LED")
        (field (name "MANUFACTURER") "OSRAM Opto Semiconductors Inc.")
        (field (name "MFG_PARTNO") "LO Q976-PS-25")
      )
      (libsource (lib "eagle-import") (part "LED_0603_AMBER_DIFF_LOQ976-PS-25"))
    )
    (comp (ref "D27")
      (value "LED_0603_AMBER_DIFF_LOQ976-PS-25")
      (footprint "eagle-import:LEDM1608X80N")
      (fields
        (field (name "CODE") "Orange LED")
        (field (name "MANUFACTURER") "OSRAM Opto Semiconductors Inc.")
        (field (name "MFG_PARTNO") "LO Q976-PS-25")
      )
      (libsource (lib "eagle-import") (part "LED_0603_AMBER_DIFF_LOQ976-PS-25"))
    )
    (comp (ref "ENCLOSURE1")
      (value "ENCLOSURE_BOPLA_BOP-500-9005-TOP")
      (footprint "eagle-import:ENCLOSURE_BOPLA_BOP-500-9005")
      (fields
        (field (name "CODE") "BOP 500-9005")
        (field (name "MANUFACTURER") "BOPLA")
        (field (name "MFG_PARTNO") "BOP 500-9005")
      )
      (libsource (lib "eagle-import") (part "ENCLOSURE_BOPLA_BOP-500-9005-TOP"))
    )
    (comp (ref "FB1")
      (value "FERRITE_0805_0A5")
      (footprint "eagle-import:RESC2012X50")
      (fields
        (field (name "CODE") "0.4 Ohm / 500 mA")
        (field (name "MANUFACTURER") "TDK")
        (field (name "MFG_PARTNO") "MMZ2012Y152B")
      )
      (libsource (lib "eagle-import") (part "FERRITE_0805_0A5"))
    )
    (comp (ref "FB2")
      (value "FERRITE_0805_0A5")
      (footprint "eagle-import:RESC2012X50")
      (fields
        (field (name "CODE") "0.4 Ohm / 500 mA")
        (field (name "MANUFACTURER") "TDK")
        (field (name "MFG_PARTNO") "MMZ2012Y152B")
      )
      (libsource (lib "eagle-import") (part "FERRITE_0805_0A5"))
    )
    (comp (ref "FB3")
      (value "FERRITE_0805_0A5")
      (footprint "eagle-import:RESC2012X50")
      (fields
        (field (name "CODE") "0.4 Ohm / 500 mA")
        (field (name "MANUFACTURER") "TDK")
        (field (name "MFG_PARTNO") "MMZ2012Y152B")
      )
      (libsource (lib "eagle-import") (part "FERRITE_0805_0A5"))
    )
    (comp (ref "FB4")
      (value "FERRITE_0805_0A5")
      (footprint "eagle-import:RESC2012X50")
      (fields
        (field (name "CODE") "0.4 Ohm / 500 mA")
        (field (name "MANUFACTURER") "TDK")
        (field (name "MFG_PARTNO") "MMZ2012Y152B")
      )
      (libsource (lib "eagle-import") (part "FERRITE_0805_0A5"))
    )
    (comp (ref "FB6")
      (value "FERRITE_0805_0A5")
      (footprint "eagle-import:RESC2012X50")
      (fields
        (field (name "CODE") "0.4 Ohm / 500 mA")
        (field (name "MANUFACTURER") "TDK")
        (field (name "MFG_PARTNO") "MMZ2012Y152B")
      )
      (libsource (lib "eagle-import") (part "FERRITE_0805_0A5"))
    )
    (comp (ref "FIDUCIAL1")
      (value "FIDUCIAL")
      (footprint "eagle-import:FIDUCIAL")
      (fields (field (name "CODE") "FIDUCIAL") (field (name "MANUFACTURER") "DNP"))
      (libsource (lib "eagle-import") (part "FIDUCIAL"))
    )
    (comp (ref "FIDUCIAL2")
      (value "FIDUCIAL")
      (footprint "eagle-import:FIDUCIAL")
      (fields (field (name "CODE") "FIDUCIAL") (field (name "MANUFACTURER") "DNP"))
      (libsource (lib "eagle-import") (part "FIDUCIAL"))
    )
    (comp (ref "FIDUCIAL3")
      (value "FIDUCIAL")
      (footprint "eagle-import:FIDUCIAL")
      (fields (field (name "CODE") "FIDUCIAL") (field (name "MANUFACTURER") "DNP"))
      (libsource (lib "eagle-import") (part "FIDUCIAL"))
    )
    (comp (ref "FIDUCIAL4")
      (value "FIDUCIAL")
      (footprint "eagle-import:FIDUCIAL")
      (fields (field (name "CODE") "FIDUCIAL") (field (name "MANUFACTURER") "DNP"))
      (libsource (lib "eagle-import") (part "FIDUCIAL"))
    )
    (comp (ref "FIDUCIAL5")
      (value "FIDUCIAL")
      (footprint "eagle-import:FIDUCIAL")
      (fields (field (name "CODE") "FIDUCIAL") (field (name "MANUFACTURER") "DNP"))
      (libsource (lib "eagle-import") (part "FIDUCIAL"))
    )
    (comp (ref "FIDUCIAL6")
      (value "FIDUCIAL")
      (footprint "eagle-import:FIDUCIAL")
      (fields (field (name "CODE") "FIDUCIAL") (field (name "MANUFACTURER") "DNP"))
      (libsource (lib "eagle-import") (part "FIDUCIAL"))
    )
    (comp (ref "H1")
      (value "SWITCH_CAP_DSA_RELEG")
      (footprint "eagle-import:SWITCH_CAP_DSA_RELEG")
      (fields
        (field (name "CODE") "Key Cap")
        (field (name "MANUFACTURER") "Pimp My Keyboard")
        (field (name "MFG_PARTNO") "DSA RELEGENDABLES")
      )
      (libsource (lib "eagle-import") (part "SWITCH_CAP_DSA_RELEG"))
    )
    (comp (ref "H2")
      (value "SWITCH_CAP_DSA_RELEG")
      (footprint "eagle-import:SWITCH_CAP_DSA_RELEG")
      (fields
        (field (name "CODE") "Key Cap")
        (field (name "MANUFACTURER") "Pimp My Keyboard")
        (field (name "MFG_PARTNO") "DSA RELEGENDABLES")
      )
      (libsource (lib "eagle-import") (part "SWITCH_CAP_DSA_RELEG"))
    )
    (comp (ref "H3")
      (value "SWITCH_CAP_DSA_RELEG")
      (footprint "eagle-import:SWITCH_CAP_DSA_RELEG")
      (fields
        (field (name "CODE") "Key Cap")
        (field (name "MANUFACTURER") "Pimp My Keyboard")
        (field (name "MFG_PARTNO") "DSA RELEGENDABLES")
      )
      (libsource (lib "eagle-import") (part "SWITCH_CAP_DSA_RELEG"))
    )
    (comp (ref "H4")
      (value "SWITCH_CAP_DSA_RELEG")
      (footprint "eagle-import:SWITCH_CAP_DSA_RELEG")
      (fields
        (field (name "CODE") "Key Cap")
        (field (name "MANUFACTURER") "Pimp My Keyboard")
        (field (name "MFG_PARTNO") "DSA RELEGENDABLES")
      )
      (libsource (lib "eagle-import") (part "SWITCH_CAP_DSA_RELEG"))
    )
    (comp (ref "H5")
      (value "SWITCH_CAP_DSA_RELEG")
      (footprint "eagle-import:SWITCH_CAP_DSA_RELEG")
      (fields
        (field (name "CODE") "Key Cap")
        (field (name "MANUFACTURER") "Pimp My Keyboard")
        (field (name "MFG_PARTNO") "DSA RELEGENDABLES")
      )
      (libsource (lib "eagle-import") (part "SWITCH_CAP_DSA_RELEG"))
    )
    (comp (ref "H6")
      (value "SWITCH_CAP_DSA_RELEG")
      (footprint "eagle-import:SWITCH_CAP_DSA_RELEG")
      (fields
        (field (name "CODE") "Key Cap")
        (field (name "MANUFACTURER") "Pimp My Keyboard")
        (field (name "MFG_PARTNO") "DSA RELEGENDABLES")
      )
      (libsource (lib "eagle-import") (part "SWITCH_CAP_DSA_RELEG"))
    )
    (comp (ref "H7")
      (value "SWITCH_CAP_DSA_RELEG")
      (footprint "eagle-import:SWITCH_CAP_DSA_RELEG")
      (fields
        (field (name "CODE") "Key Cap")
        (field (name "MANUFACTURER") "Pimp My Keyboard")
        (field (name "MFG_PARTNO") "DSA RELEGENDABLES")
      )
      (libsource (lib "eagle-import") (part "SWITCH_CAP_DSA_RELEG"))
    )
    (comp (ref "H8")
      (value "SWITCH_CAP_DSA_RELEG")
      (footprint "eagle-import:SWITCH_CAP_DSA_RELEG")
      (fields
        (field (name "CODE") "Key Cap")
        (field (name "MANUFACTURER") "Pimp My Keyboard")
        (field (name "MFG_PARTNO") "DSA RELEGENDABLES")
      )
      (libsource (lib "eagle-import") (part "SWITCH_CAP_DSA_RELEG"))
    )
    (comp (ref "L1")
      (value "L_CHOKE_EXC-34CE670U")
      (footprint "eagle-import:IND_CHOKE_EXC-34")
      (fields
        (field (name "CODE") "EXC-34CE670U")
        (field (name "MANUFACTURER") "Panasonic")
        (field (name "MFG_PARTNO") "EXC-34CE670U")
      )
      (libsource (lib "eagle-import") (part "L_CHOKE_EXC-34CE670U"))
    )
    (comp (ref "LOGO2")
      (value "ART_LOGO_TEXT_2.5MM-SILK")
      (footprint "eagle-import:ART_LOGO_TEXT_2.5MM_SILK")
      (fields (field (name "CODE") "Logo text 2.5mm silk") (field (name "MANUFACTURER") "DNP"))
      (libsource (lib "eagle-import") (part "ART_LOGO_TEXT_2.5MM-SILK"))
    )
    (comp (ref "R1")
      (value "R0805_10K_5%")
      (footprint "eagle-import:RESC2012X50")
      (fields
        (field (name "CODE") "10k")
        (field (name "MANUFACTURER") "Bourns Inc.")
        (field (name "MFG_PARTNO") "CR0805-JW-103ELF")
      )
      (libsource (lib "eagle-import") (part "R0805_10K_5%"))
    )
    (comp (ref "R2")
      (value "R0805_1K_1%")
      (footprint "eagle-import:RESC2012X50")
      (fields
        (field (name "CODE") "1k")
        (field (name "MANUFACTURER") "Yageo")
        (field (name "MFG_PARTNO") "RC0805FR-071KL")
      )
      (libsource (lib "eagle-import") (part "R0805_1K_1%"))
    )
    (comp (ref "R3")
      (value "R0805_1K_1%")
      (footprint "eagle-import:RESC2012X50")
      (fields
        (field (name "CODE") "1k")
        (field (name "MANUFACTURER") "Yageo")
        (field (name "MFG_PARTNO") "RC0805FR-071KL")
      )
      (libsource (lib "eagle-import") (part "R0805_1K_1%"))
    )
    (comp (ref "R4")
      (value "R0603_22")
      (footprint "eagle-import:RESC1608X45N")
      (fields
        (field (name "CODE") "22")
        (field (name "MANUFACTURER") "Panasonic")
        (field (name "MFG_PARTNO") "ERJ-3EKF22R0V")
      )
      (libsource (lib "eagle-import") (part "R0603_22"))
    )
    (comp (ref "R5")
      (value "R0603_22")
      (footprint "eagle-import:RESC1608X45N")
      (fields
        (field (name "CODE") "22")
        (field (name "MANUFACTURER") "Panasonic")
        (field (name "MFG_PARTNO") "ERJ-3EKF22R0V")
      )
      (libsource (lib "eagle-import") (part "R0603_22"))
    )
    (comp (ref "R6")
      (value "R0805_1M_5%")
      (footprint "eagle-import:RESC2012X50")
      (fields
        (field (name "CODE") "1M")
        (field (name "MANUFACTURER") "Yageo")
        (field (name "MFG_PARTNO") "RC0805JR-071ML")
      )
      (libsource (lib "eagle-import") (part "R0805_1M_5%"))
    )
    (comp (ref "R7")
      (value "R0805_10K_5%")
      (footprint "eagle-import:RESC2012X50")
      (fields
        (field (name "CODE") "10k")
        (field (name "MANUFACTURER") "Bourns Inc.")
        (field (name "MFG_PARTNO") "CR0805-JW-103ELF")
      )
      (libsource (lib "eagle-import") (part "R0805_10K_5%"))
    )
    (comp (ref "R8")
      (value "R0805_200_1%")
      (footprint "eagle-import:RESC2012X50")
      (fields
        (field (name "CODE") "200")
        (field (name "MANUFACTURER") "Yageo")
        (field (name "MFG_PARTNO") "RC0805FR-07200RL")
      )
      (libsource (lib "eagle-import") (part "R0805_200_1%"))
    )
    (comp (ref "R9")
      (value "R0805_200_1%")
      (footprint "eagle-import:RESC2012X50")
      (fields
        (field (name "CODE") "200")
        (field (name "MANUFACTURER") "Yageo")
        (field (name "MFG_PARTNO") "RC0805FR-07200RL")
      )
      (libsource (lib "eagle-import") (part "R0805_200_1%"))
    )
    (comp (ref "R10")
      (value "R0805_200_1%")
      (footprint "eagle-import:RESC2012X50")
      (fields
        (field (name "CODE") "200")
        (field (name "MANUFACTURER") "Yageo")
        (field (name "MFG_PARTNO") "RC0805FR-07200RL")
      )
      (libsource (lib "eagle-import") (part "R0805_200_1%"))
    )
    (comp (ref "R11")
      (value "R0805_200_1%")
      (footprint "eagle-import:RESC2012X50")
      (fields
        (field (name "CODE") "200")
        (field (name "MANUFACTURER") "Yageo")
        (field (name "MFG_PARTNO") "RC0805FR-07200RL")
      )
      (libsource (lib "eagle-import") (part "R0805_200_1%"))
    )
    (comp (ref "R12")
      (value "R0805_200_1%")
      (footprint "eagle-import:RESC2012X50")
      (fields
        (field (name "CODE") "200")
        (field (name "MANUFACTURER") "Yageo")
        (field (name "MFG_PARTNO") "RC0805FR-07200RL")
      )
      (libsource (lib "eagle-import") (part "R0805_200_1%"))
    )
    (comp (ref "R13")
      (value "R0805_1K_1%")
      (footprint "eagle-import:RESC2012X50")
      (fields
        (field (name "CODE") "1k")
        (field (name "MANUFACTURER") "Yageo")
        (field (name "MFG_PARTNO") "RC0805FR-071KL")
      )
      (libsource (lib "eagle-import") (part "R0805_1K_1%"))
    )
    (comp (ref "R14")
      (value "R0805_200_1%")
      (footprint "eagle-import:RESC2012X50")
      (fields
        (field (name "CODE") "200")
        (field (name "MANUFACTURER") "Yageo")
        (field (name "MFG_PARTNO") "RC0805FR-07200RL")
      )
      (libsource (lib "eagle-import") (part "R0805_200_1%"))
    )
    (comp (ref "R15")
      (value "R0805_200_1%")
      (footprint "eagle-import:RESC2012X50")
      (fields
        (field (name "CODE") "200")
        (field (name "MANUFACTURER") "Yageo")
        (field (name "MFG_PARTNO") "RC0805FR-07200RL")
      )
      (libsource (lib "eagle-import") (part "R0805_200_1%"))
    )
    (comp (ref "R16")
      (value "R0402_DNP")
      (footprint "eagle-import:RESC1005X35N")
      (fields (field (name "CODE") "DNP") (field (name "MANUFACTURER") "DNP"))
      (libsource (lib "eagle-import") (part "R0402_DNP"))
    )
    (comp (ref "R17")
      (value "R0805_3K3_1%")
      (footprint "eagle-import:RESC2012X50")
      (fields
        (field (name "CODE") "3k3")
        (field (name "MANUFACTURER") "Yageo")
        (field (name "MFG_PARTNO") "RC0805FR-073K3L")
      )
      (libsource (lib "eagle-import") (part "R0805_3K3_1%"))
    )
    (comp (ref "R18")
      (value "R0805_1K_1%")
      (footprint "eagle-import:RESC2012X50")
      (fields
        (field (name "CODE") "1k")
        (field (name "MANUFACTURER") "Yageo")
        (field (name "MFG_PARTNO") "RC0805FR-071KL")
      )
      (libsource (lib "eagle-import") (part "R0805_1K_1%"))
    )
    (comp (ref "R19")
      (value "R0805_200_1%")
      (footprint "eagle-import:RESC2012X50")
      (fields
        (field (name "CODE") "200")
        (field (name "MANUFACTURER") "Yageo")
        (field (name "MFG_PARTNO") "RC0805FR-07200RL")
      )
      (libsource (lib "eagle-import") (part "R0805_200_1%"))
    )
    (comp (ref "R20")
      (value "R0805_3K3_1%")
      (footprint "eagle-import:RESC2012X50")
      (fields
        (field (name "CODE") "3k3")
        (field (name "MANUFACTURER") "Yageo")
        (field (name "MFG_PARTNO") "RC0805FR-073K3L")
      )
      (libsource (lib "eagle-import") (part "R0805_3K3_1%"))
    )
    (comp (ref "R21")
      (value "R0805_200_1%")
      (footprint "eagle-import:RESC2012X50")
      (fields
        (field (name "CODE") "200")
        (field (name "MANUFACTURER") "Yageo")
        (field (name "MFG_PARTNO") "RC0805FR-07200RL")
      )
      (libsource (lib "eagle-import") (part "R0805_200_1%"))
    )
    (comp (ref "R22")
      (value "R0805_200_1%")
      (footprint "eagle-import:RESC2012X50")
      (fields
        (field (name "CODE") "200")
        (field (name "MANUFACTURER") "Yageo")
        (field (name "MFG_PARTNO") "RC0805FR-07200RL")
      )
      (libsource (lib "eagle-import") (part "R0805_200_1%"))
    )
    (comp (ref "R23")
      (value "R0805_1K_1%")
      (footprint "eagle-import:RESC2012X50")
      (fields
        (field (name "CODE") "1k")
        (field (name "MANUFACTURER") "Yageo")
        (field (name "MFG_PARTNO") "RC0805FR-071KL")
      )
      (libsource (lib "eagle-import") (part "R0805_1K_1%"))
    )
    (comp (ref "R24")
      (value "R0603_0")
      (footprint "eagle-import:RESC1608X45N")
      (fields
        (field (name "CODE") "0")
        (field (name "MANUFACTURER") "Panasonic")
        (field (name "MFG_PARTNO") "ERJ-3GEY0R00V")
      )
      (libsource (lib "eagle-import") (part "R0603_0"))
    )
    (comp (ref "R25")
      (value "R0805_1K_1%")
      (footprint "eagle-import:RESC2012X50")
      (fields
        (field (name "CODE") "1k")
        (field (name "MANUFACTURER") "Yageo")
        (field (name "MFG_PARTNO") "RC0805FR-071KL")
      )
      (libsource (lib "eagle-import") (part "R0805_1K_1%"))
    )
    (comp (ref "R26")
      (value "R0805_1K_1%")
      (footprint "eagle-import:RESC2012X50")
      (fields
        (field (name "CODE") "1k")
        (field (name "MANUFACTURER") "Yageo")
        (field (name "MFG_PARTNO") "RC0805FR-071KL")
      )
      (libsource (lib "eagle-import") (part "R0805_1K_1%"))
    )
    (comp (ref "R27")
      (value "R0805_1K_1%")
      (footprint "eagle-import:RESC2012X50")
      (fields
        (field (name "CODE") "1k")
        (field (name "MANUFACTURER") "Yageo")
        (field (name "MFG_PARTNO") "RC0805FR-071KL")
      )
      (libsource (lib "eagle-import") (part "R0805_1K_1%"))
    )
    (comp (ref "R28")
      (value "R0805_1K_1%")
      (footprint "eagle-import:RESC2012X50")
      (fields
        (field (name "CODE") "1k")
        (field (name "MANUFACTURER") "Yageo")
        (field (name "MFG_PARTNO") "RC0805FR-071KL")
      )
      (libsource (lib "eagle-import") (part "R0805_1K_1%"))
    )
    (comp (ref "R29")
      (value "R0805_1K_1%")
      (footprint "eagle-import:RESC2012X50")
      (fields
        (field (name "CODE") "1k")
        (field (name "MANUFACTURER") "Yageo")
        (field (name "MFG_PARTNO") "RC0805FR-071KL")
      )
      (libsource (lib "eagle-import") (part "R0805_1K_1%"))
    )
    (comp (ref "R30")
      (value "R0805_1K_1%")
      (footprint "eagle-import:RESC2012X50")
      (fields
        (field (name "CODE") "1k")
        (field (name "MANUFACTURER") "Yageo")
        (field (name "MFG_PARTNO") "RC0805FR-071KL")
      )
      (libsource (lib "eagle-import") (part "R0805_1K_1%"))
    )
    (comp (ref "R31")
      (value "R0805_200_1%")
      (footprint "eagle-import:RESC2012X50")
      (fields
        (field (name "CODE") "200")
        (field (name "MANUFACTURER") "Yageo")
        (field (name "MFG_PARTNO") "RC0805FR-07200RL")
      )
      (libsource (lib "eagle-import") (part "R0805_200_1%"))
    )
    (comp (ref "R32")
      (value "R0603_0")
      (footprint "eagle-import:RESC1608X45N")
      (fields
        (field (name "CODE") "0")
        (field (name "MANUFACTURER") "Panasonic")
        (field (name "MFG_PARTNO") "ERJ-3GEY0R00V")
      )
      (libsource (lib "eagle-import") (part "R0603_0"))
    )
    (comp (ref "R33")
      (value "R0603_0")
      (footprint "eagle-import:RESC1608X45N")
      (fields
        (field (name "CODE") "0")
        (field (name "MANUFACTURER") "Panasonic")
        (field (name "MFG_PARTNO") "ERJ-3GEY0R00V")
      )
      (libsource (lib "eagle-import") (part "R0603_0"))
    )
    (comp (ref "S1")
      (value "SWITCH_BUTTON_MX1A-C1NW")
      (footprint "eagle-import:SWITCH_BUTTON_CHERRY_MX")
      (fields
        (field (name "CODE") "MX1A-C1NW")
        (field (name "MANUFACTURER") "Cherry")
        (field (name "MFG_PARTNO") "MX1A-C1NW")
      )
      (libsource (lib "eagle-import") (part "SWITCH_BUTTON_MX1A-C1NW"))
    )
    (comp (ref "S3")
      (value "SWITCH_BUTTON_MX1A-C1NW")
      (footprint "eagle-import:SWITCH_BUTTON_CHERRY_MX")
      (fields
        (field (name "CODE") "MX1A-C1NW")
        (field (name "MANUFACTURER") "Cherry")
        (field (name "MFG_PARTNO") "MX1A-C1NW")
      )
      (libsource (lib "eagle-import") (part "SWITCH_BUTTON_MX1A-C1NW"))
    )
    (comp (ref "S4")
      (value "SWITCH_BUTTON_MX1A-C1NW")
      (footprint "eagle-import:SWITCH_BUTTON_CHERRY_MX")
      (fields
        (field (name "CODE") "MX1A-C1NW")
        (field (name "MANUFACTURER") "Cherry")
        (field (name "MFG_PARTNO") "MX1A-C1NW")
      )
      (libsource (lib "eagle-import") (part "SWITCH_BUTTON_MX1A-C1NW"))
    )
    (comp (ref "S5")
      (value "SWITCH_BUTTON_MX1A-C1NW")
      (footprint "eagle-import:SWITCH_BUTTON_CHERRY_MX")
      (fields
        (field (name "CODE") "MX1A-C1NW")
        (field (name "MANUFACTURER") "Cherry")
        (field (name "MFG_PARTNO") "MX1A-C1NW")
      )
      (libsource (lib "eagle-import") (part "SWITCH_BUTTON_MX1A-C1NW"))
    )
    (comp (ref "S6")
      (value "SWITCH_BUTTON_MX1A-C1NW")
      (footprint "eagle-import:SWITCH_BUTTON_CHERRY_MX")
      (fields
        (field (name "CODE") "MX1A-C1NW")
        (field (name "MANUFACTURER") "Cherry")
        (field (name "MFG_PARTNO") "MX1A-C1NW")
      )
      (libsource (lib "eagle-import") (part "SWITCH_BUTTON_MX1A-C1NW"))
    )
    (comp (ref "S7")
      (value "SWITCH_BUTTON_MX1A-C1NW")
      (footprint "eagle-import:SWITCH_BUTTON_CHERRY_MX")
      (fields
        (field (name "CODE") "MX1A-C1NW")
        (field (name "MANUFACTURER") "Cherry")
        (field (name "MFG_PARTNO") "MX1A-C1NW")
      )
      (libsource (lib "eagle-import") (part "SWITCH_BUTTON_MX1A-C1NW"))
    )
    (comp (ref "S8")
      (value "SWITCH_BUTTON_MX1A-C1NW")
      (footprint "eagle-import:SWITCH_BUTTON_CHERRY_MX")
      (fields
        (field (name "CODE") "MX1A-C1NW")
        (field (name "MANUFACTURER") "Cherry")
        (field (name "MFG_PARTNO") "MX1A-C1NW")
      )
      (libsource (lib "eagle-import") (part "SWITCH_BUTTON_MX1A-C1NW"))
    )
    (comp (ref "S9")
      (value "SWITCH_BUTTON_MX1A-C1NW")
      (footprint "eagle-import:SWITCH_BUTTON_CHERRY_MX")
      (fields
        (field (name "CODE") "MX1A-C1NW")
        (field (name "MANUFACTURER") "Cherry")
        (field (name "MFG_PARTNO") "MX1A-C1NW")
      )
      (libsource (lib "eagle-import") (part "SWITCH_BUTTON_MX1A-C1NW"))
    )
    (comp (ref "S10")
      (value "SWITCH_MOM_SPST_FSM4JSMA")
      (footprint "eagle-import:SWITCH_BUTTON_TE_FSM4JSMA")
      (fields
        (field (name "CODE") "Button")
        (field (name "MANUFACTURER") "TE Connectivity")
        (field (name "MFG_PARTNO") "FSM4JSMA")
      )
      (libsource (lib "eagle-import") (part "SWITCH_MOM_SPST_FSM4JSMA"))
    )
    (comp (ref "TP1")
      (value "PAD_TEST_POINT-2.5/0.7_A")
      (footprint "eagle-import:TEST_POINT_2.5MM_0.7HOLE_1SIDE")
      (fields
        (field (name "MANUFACTURER") "Do not populate")
        (field (name "MFG_PARTNO") "DNP")
        (field (name "INFO") "CLK 3V3")
      )
      (libsource (lib "eagle-import") (part "PAD_TEST_POINT-2.5/0.7_A"))
    )
    (comp (ref "TP2")
      (value "PAD_TEST_POINT-2.5/0.7_A")
      (footprint "eagle-import:TEST_POINT_2.5MM_0.7HOLE_1SIDE")
      (fields
        (field (name "INFO") "Edit \"INFO\" attribute")
        (field (name "MANUFACTURER") "Do not populate")
        (field (name "MFG_PARTNO") "DNP")
        (field (name "INFO_1") "CLK 5 V")
      )
      (libsource (lib "eagle-import") (part "PAD_TEST_POINT-2.5/0.7_A"))
    )
    (comp (ref "TP3")
      (value "PAD_TEST_POINT-2.5/0.7_A")
      (footprint "eagle-import:TEST_POINT_2.5MM_0.7HOLE_1SIDE")
      (fields
        (field (name "INFO") "Edit \"INFO\" attribute")
        (field (name "MANUFACTURER") "Do not populate")
        (field (name "MFG_PARTNO") "DNP")
        (field (name "INFO_1") "3V3")
      )
      (libsource (lib "eagle-import") (part "PAD_TEST_POINT-2.5/0.7_A"))
    )
    (comp (ref "TP5")
      (value "PAD_TEST_POINT-2.5/0.7_A")
      (footprint "eagle-import:TEST_POINT_2.5MM_0.7HOLE_1SIDE")
      (fields
        (field (name "INFO") "Edit \"INFO\" attribute")
        (field (name "MANUFACTURER") "Do not populate")
        (field (name "MFG_PARTNO") "DNP")
        (field (name "INFO_1") "!RESET")
      )
      (libsource (lib "eagle-import") (part "PAD_TEST_POINT-2.5/0.7_A"))
    )
    (comp (ref "TP7")
      (value "PAD_TEST_POINT-2.5/0.7_A")
      (footprint "eagle-import:TEST_POINT_2.5MM_0.7HOLE_1SIDE")
      (fields
        (field (name "INFO") "Edit \"INFO\" attribute")
        (field (name "MANUFACTURER") "Do not populate")
        (field (name "MFG_PARTNO") "DNP")
        (field (name "INFO_1") "5 V")
      )
      (libsource (lib "eagle-import") (part "PAD_TEST_POINT-2.5/0.7_A"))
    )
    (comp (ref "TP15")
      (value "PAD_TEST_POINT-2.5/0.7_A")
      (footprint "eagle-import:TEST_POINT_2.5MM_0.7HOLE_1SIDE")
      (fields
        (field (name "MANUFACTURER") "Do not populate")
        (field (name "MFG_PARTNO") "DNP")
        (field (name "INFO") "CLK_5V")
      )
      (libsource (lib "eagle-import") (part "PAD_TEST_POINT-2.5/0.7_A"))
    )
    (comp (ref "TP16")
      (value "PAD_TEST_POINT-2.5/0.7_A")
      (footprint "eagle-import:TEST_POINT_2.5MM_0.7HOLE_1SIDE")
      (fields
        (field (name "INFO") "Edit \"INFO\" attribute")
        (field (name "MANUFACTURER") "Do not populate")
        (field (name "MFG_PARTNO") "DNP")
        (field (name "INFO_1") "MISO")
      )
      (libsource (lib "eagle-import") (part "PAD_TEST_POINT-2.5/0.7_A"))
    )
    (comp (ref "TP17")
      (value "PAD_TEST_POINT-2.5/0.7_A")
      (footprint "eagle-import:TEST_POINT_2.5MM_0.7HOLE_1SIDE")
      (fields
        (field (name "INFO") "Edit \"INFO\" attribute")
        (field (name "MANUFACTURER") "Do not populate")
        (field (name "MFG_PARTNO") "DNP")
        (field (name "INFO_1") "MOSI_5V")
      )
      (libsource (lib "eagle-import") (part "PAD_TEST_POINT-2.5/0.7_A"))
    )
    (comp (ref "U1")
      (value "IC_MCU_ATMEGA32U4-AU")
      (footprint "eagle-import:QFP80P1000X1000X120-44R_N")
      (fields
        (field (name "CODE") "ATMEGA32U4")
        (field (name "MANUFACTURER") "Microchip")
        (field (name "MFG_PARTNO") "ATMEGA32U4-AU")
      )
      (libsource (lib "eagle-import") (part "IC_MCU_ATMEGA32U4-AU"))
    )
    (comp (ref "U2")
      (value "IC_MEM_FLASH_AT45DB321E")
      (footprint "eagle-import:SOP127P800X175-8")
      (fields
        (field (name "CODE") "AT45DB321E-SHF-T ")
        (field (name "MANUFACTURER") "Adesto Technologies")
        (field (name "MFG_PARTNO") "AT45DB321E-SHF-T ")
      )
      (libsource (lib "eagle-import") (part "IC_MEM_FLASH_AT45DB321E"))
    )
    (comp (ref "U3")
      (value "IC_REG_3V3_1A_NCP1117LPST33T3G")
      (footprint "eagle-import:SOT223")
      (fields
        (field (name "CODE") "1117-3v3")
        (field (name "MANUFACTURER") "ON Semiconductor")
        (field (name "MFG_PARTNO") "NCP1117LPST33T3G")
      )
      (libsource (lib "eagle-import") (part "IC_REG_3V3_1A_NCP1117LPST33T3G"))
    )
    (comp (ref "U4")
      (value "IC_LEVEL_SHIFTER_SN74LVC2T45")
      (footprint "eagle-import:SOP65P400X130-8")
      (fields
        (field (name "CODE") "SN74LVC2T45DCTT")
        (field (name "MANUFACTURER") "Texas Instruments")
        (field (name "MFG_PARTNO") "SN74LVC2T45DCTT")
      )
      (libsource (lib "eagle-import") (part "IC_LEVEL_SHIFTER_SN74LVC2T45"))
    )
    (comp (ref "U5")
      (value "IC_LEVEL_SHIFTER_SN74LVC2T45")
      (footprint "eagle-import:SOP65P400X130-8")
      (fields
        (field (name "CODE") "SN74LVC2T45DCTT")
        (field (name "MANUFACTURER") "Texas Instruments")
        (field (name "MFG_PARTNO") "SN74LVC2T45DCTT")
      )
      (libsource (lib "eagle-import") (part "IC_LEVEL_SHIFTER_SN74LVC2T45"))
    )
    (comp (ref "U6")
      (value "IC_LEVEL_SHIFTER_SN74LVC2T45")
      (footprint "eagle-import:SOP65P400X130-8")
      (fields
        (field (name "CODE") "SN74LVC2T45DCTT")
        (field (name "MANUFACTURER") "Texas Instruments")
        (field (name "MFG_PARTNO") "SN74LVC2T45DCTT")
      )
      (libsource (lib "eagle-import") (part "IC_LEVEL_SHIFTER_SN74LVC2T45"))
    )
    (comp (ref "X1")
      (value "CON_USB_MICROB_UJ2-MIBH-4-SMT-TR-MAN")
      (footprint "eagle-import:CON_USB_MICROB_UJ2-MIBH-4-SMT-TR_MAN")
      (fields
        (field (name "CODE") "UJ2-MIBH-4-SMT-TR")
        (field (name "MANUFACTURER") "CUI")
        (field (name "MFG_PARTNO") "UJ2-MIBH-4-SMT-TR")
      )
      (libsource (lib "eagle-import") (part "CON_USB_MICROB_UJ2-MIBH-4-SMT-TR-MAN"))
    )
    (comp (ref "X2")
      (value "CON_PROG_AVR_ISP-OFFSET_1X06")
      (footprint "eagle-import:CON_PINHD_1X06_TH_OFFSET")
      (fields (field (name "CODE") "1x06 offset") (field (name "MANUFACTURER") "DNP"))
      (libsource (lib "eagle-import") (part "CON_PROG_AVR_ISP-OFFSET_1X06"))
    )
    (comp (ref "X3")
      (value "CON_1X04_TH_OFFSET_PADS-SILK")
      (footprint "eagle-import:1X04_TH_OFFSET")
      (fields (field (name "CODE") "1X04") (field (name "MANUFACTURER") "DNP"))
      (libsource (lib "eagle-import") (part "CON_1X04_TH_OFFSET_PADS-SILK"))
    )
    (comp (ref "X4")
      (value "HOL_3.2/6.0_NP")
      (footprint "eagle-import:MTG_NP_M3_320X600")
      (fields (field (name "CODE") "NP 3.2 mm") (field (name "MANUFACTURER") "DNP"))
      (libsource (lib "eagle-import") (part "HOL_3.2/6.0_NP"))
    )
    (comp (ref "X6")
      (value "HOL_3.2/6.0_NP")
      (footprint "eagle-import:MTG_NP_M3_320X600")
      (fields (field (name "CODE") "NP 3.2 mm") (field (name "MANUFACTURER") "DNP"))
      (libsource (lib "eagle-import") (part "HOL_3.2/6.0_NP"))
    )
    (comp (ref "X9")
      (value "HOL_3.2/6.0_NP")
      (footprint "eagle-import:MTG_NP_M3_320X600")
      (fields (field (name "CODE") "NP 3.2 mm") (field (name "MANUFACTURER") "DNP"))
      (libsource (lib "eagle-import") (part "HOL_3.2/6.0_NP"))
    )
    (comp (ref "X10")
      (value "HOL_3.2/6.0_NP")
      (footprint "eagle-import:MTG_NP_M3_320X600")
      (fields (field (name "CODE") "NP 3.2 mm") (field (name "MANUFACTURER") "DNP"))
      (libsource (lib "eagle-import") (part "HOL_3.2/6.0_NP"))
    )
    (comp (ref "X11")
      (value "CON_MICROSD_MOLEX_5033981892-M")
      (footprint "eagle-import:CON_MICROSD_MOLEX_5033981892_M")
      (fields
        (field (name "CODE") "503398-1892")
        (field (name "MANUFACTURER") "Molex")
        (field (name "MFG_PARTNO") "5033981892")
      )
      (libsource (lib "eagle-import") (part "CON_MICROSD_MOLEX_5033981892-M"))
    )
    (comp (ref "X12")
      (value "HOL_3.2/6.0_NP")
      (footprint "eagle-import:MTG_NP_M3_320X600")
      (fields (field (name "CODE") "NP 3.2 mm") (field (name "MANUFACTURER") "DNP"))
      (libsource (lib "eagle-import") (part "HOL_3.2/6.0_NP"))
    )
    (comp (ref "X13")
      (value "PAD_TEST_GROUND_HOOK")
      (footprint "eagle-import:PAD_GND_HOOK_M")
      (fields (field (name "MANUFACTURER") "Do not populate") (field (name "MFG_PARTNO") "DNP"))
      (libsource (lib "eagle-import") (part "PAD_TEST_GROUND_HOOK"))
    )
    (comp (ref "X14")
      (value "CON_CLAMP_PTSM_1X04_H_SMD")
      (footprint "eagle-import:CON_PHOENIX_CONTACT_1702474")
      (fields
        (field (name "CODE") "1702474")
        (field (name "MANUFACTURER") "Phoenix Contact")
        (field (name "MFG_PARTNO") "1702474")
      )
      (libsource (lib "eagle-import") (part "CON_CLAMP_PTSM_1X04_H_SMD"))
    )
    (comp (ref "X15")
      (value "CON_CLAMP_PTSM_1X08_H_SMD")
      (footprint "eagle-import:CON_PHOENIX_CONTACT_1771088")
      (fields
        (field (name "CODE") "1771088")
        (field (name "MANUFACTURER") "Phoenix Contact")
        (field (name "MFG_PARTNO") "1771088")
      )
      (libsource (lib "eagle-import") (part "CON_CLAMP_PTSM_1X08_H_SMD"))
    )
    (comp (ref "X17")
      (value "HOL_3.2/6.0_NP")
      (footprint "eagle-import:MTG_NP_M3_320X600")
      (fields (field (name "CODE") "NP 3.2 mm") (field (name "MANUFACTURER") "DNP"))
      (libsource (lib "eagle-import") (part "HOL_3.2/6.0_NP"))
    )
    (comp (ref "X18")
      (value "HOL_3.2/6.0_NP")
      (footprint "eagle-import:MTG_NP_M3_320X600")
      (fields (field (name "CODE") "NP 3.2 mm") (field (name "MANUFACTURER") "DNP"))
      (libsource (lib "eagle-import") (part "HOL_3.2/6.0_NP"))
    )
    (comp (ref "Y1")
      (value "OSC_CRYSTAL_16M_ABLS-16.000MHZ-B4-T-HC49")
      (footprint "eagle-import:OSC_CRYSTAL_HC49_US")
      (fields
        (field (name "CODE") "16M")
        (field (name "MANUFACTURER") "Abracon LLC")
        (field (name "MFG_PARTNO") "ABLS-16.000MHZ-B4-T")
      )
      (libsource (lib "eagle-import") (part "OSC_CRYSTAL_16M_ABLS-16.000MHZ-B4-T-HC49"))
    )
  )
  (nets
    (net (code "1") (name "+3V3") (class "Default")
      (node (ref "C19") (pin "P$2") (pinfunction "2_P$2") (pintype "passive"))
      (node (ref "C20") (pin "P$2") (pinfunction "2_P$2") (pintype "passive"))
      (node (ref "C28") (pin "P$1") (pinfunction "1_P$1") (pintype "passive"))
      (node (ref "C29") (pin "P$1") (pinfunction "1_P$1") (pintype "passive"))
      (node (ref "C31") (pin "P$1") (pinfunction "1_P$1") (pintype "passive"))
      (node (ref "C34") (pin "P$1") (pinfunction "1_P$1") (pintype "passive"))
      (node (ref "C44") (pin "P$1") (pinfunction "1_P$1") (pintype "passive"))
      (node (ref "C46") (pin "P$2") (pinfunction "2_P$2") (pintype "passive"))
      (node (ref "C9") (pin "P$2") (pinfunction "2_P$2") (pintype "passive"))
      (node (ref "R32") (pin "P$2") (pinfunction "2_P$2") (pintype "passive"))
      (node (ref "R33") (pin "P$2") (pinfunction "2_P$2") (pintype "passive"))
      (node (ref "TP3") (pin "P$1") (pinfunction "P$1_P$1") (pintype "bidirectional"))
      (node (ref "U2") (pin "6") (pinfunction "V+_6") (pintype "bidirectional"))
      (node (ref "U3") (pin "2") (pinfunction "VO_2") (pintype "passive"))
      (node (ref "U3") (pin "4") (pinfunction "VO_4") (pintype "passive"))
      (node (ref "U4") (pin "8") (pinfunction "VB_8") (pintype "power_in"))
      (node (ref "U5") (pin "8") (pinfunction "VB_8") (pintype "power_in"))
      (node (ref "U6") (pin "8") (pinfunction "VB_8") (pintype "power_in"))
      (node (ref "X11") (pin "4") (pinfunction "VDD_4") (pintype "bidirectional"))
    )
    (net (code "2") (name "+5V") (class "Default")
      (node (ref "C12") (pin "P$1") (pinfunction "1_P$1") (pintype "passive"))
      (node (ref "C21") (pin "P$2") (pinfunction "2_P$2") (pintype "passive"))
      (node (ref "C3") (pin "P$1") (pinfunction "1_P$1") (pintype "passive"))
      (node (ref "C30") (pin "P$2") (pinfunction "2_P$2") (pintype "passive"))
      (node (ref "C32") (pin "P$1") (pinfunction "1_P$1") (pintype "passive"))
      (node (ref "C33") (pin "P$2") (pinfunction "2_P$2") (pintype "passive"))
      (node (ref "C4") (pin "P$1") (pinfunction "1_P$1") (pintype "passive"))
      (node (ref "C48") (pin "P$1") (pinfunction "1_P$1") (pintype "passive"))
      (node (ref "C5") (pin "P$1") (pinfunction "1_P$1") (pintype "passive"))
      (node (ref "C6") (pin "P$1") (pinfunction "1_P$1") (pintype "passive"))
      (node (ref "D1") (pin "5") (pinfunction "V+_5") (pintype "bidirectional"))
      (node (ref "D2") (pin "C") (pinfunction "K_C") (pintype "passive"))
      (node (ref "FB1") (pin "P$2") (pinfunction "2_P$2") (pintype "passive"))
      (node (ref "FB3") (pin "P$1") (pinfunction "1_P$1") (pintype "passive"))
      (node (ref "FB6") (pin "P$2") (pinfunction "2_P$2") (pintype "passive"))
      (node (ref "R1") (pin "P$2") (pinfunction "2_P$2") (pintype "passive"))
      (node (ref "R16") (pin "P$2") (pinfunction "2_P$2") (pintype "passive"))
      (node (ref "R17") (pin "P$2") (pinfunction "2_P$2") (pintype "passive"))
      (node (ref "R20") (pin "P$2") (pinfunction "2_P$2") (pintype "passive"))
      (node (ref "R23") (pin "P$2") (pinfunction "2_P$2") (pintype "passive"))
      (node (ref "TP7") (pin "P$1") (pinfunction "P$1_P$1") (pintype "bidirectional"))
      (node (ref "U1") (pin "14") (pinfunction "VCC_14") (pintype "bidirectional"))
      (node (ref "U1") (pin "2") (pinfunction "UVCC_2") (pintype "bidirectional"))
      (node (ref "U1") (pin "34") (pinfunction "VCC1_34") (pintype "bidirectional"))
      (node (ref "U3") (pin "3") (pinfunction "VI_3") (pintype "input"))
      (node (ref "U4") (pin "1") (pinfunction "VA_1") (pintype "power_in"))
      (node (ref "U4") (pin "5") (pinfunction "DIR_5") (pintype "input"))
      (node (ref "U5") (pin "1") (pinfunction "VA_1") (pintype "power_in"))
      (node (ref "U6") (pin "1") (pinfunction "VA_1") (pintype "power_in"))
      (node (ref "U6") (pin "5") (pinfunction "DIR_5") (pintype "input"))
    )
    (net (code "3") (name "/~{CS}_FLASH_3V3") (class "Default")
      (node (ref "U2") (pin "4") (pinfunction "~{CS}_4") (pintype "bidirectional"))
      (node (ref "U6") (pin "6") (pinfunction "B2_6") (pintype "bidirectional"))
    )
    (net (code "4") (name "/~{CS}_FLASH_5V") (class "Default")
      (node (ref "U1") (pin "31") (pinfunction "PC6(OC3A/~{OC4A})_31") (pintype "bidirectional"))
      (node (ref "U6") (pin "3") (pinfunction "A2_3") (pintype "bidirectional"))
    )
    (net (code "5") (name "/~{CS}_SD_3V3") (class "Default")
      (node (ref "U6") (pin "7") (pinfunction "B1_7") (pintype "bidirectional"))
      (node (ref "X11") (pin "2") (pinfunction "CD/DAT3_2") (pintype "bidirectional"))
    )
    (net (code "6") (name "/~{CS}_SD_5V") (class "Default")
      (node (ref "U1") (pin "25") (pinfunction "PD4(ICP1/ADC8)_25") (pintype "bidirectional"))
      (node (ref "U6") (pin "2") (pinfunction "A1_2") (pintype "bidirectional"))
    )
    (net (code "7") (name "/~{RESET}") (class "Default")
      (node (ref "R1") (pin "P$1") (pinfunction "1_P$1") (pintype "passive"))
      (node (ref "S10") (pin "1") (pinfunction "P$1_1") (pintype "bidirectional"))
      (node (ref "TP5") (pin "P$1") (pinfunction "P$1_P$1") (pintype "bidirectional"))
      (node (ref "U1") (pin "13") (pinfunction "~{RESET}_13") (pintype "bidirectional"))
      (node (ref "X2") (pin "5") (pinfunction "RST_5") (pintype "output"))
      (node (ref "X3") (pin "1") (pinfunction "1_1") (pintype "passive"))
    )
    (net (code "8") (name "/~{RESET}_3V3") (class "Default")
      (node (ref "R32") (pin "P$1") (pinfunction "1_P$1") (pintype "passive"))
      (node (ref "U2") (pin "3") (pinfunction "~{RESET}_3") (pintype "bidirectional"))
    )
    (net (code "9") (name "AD0") (class "Default")
      (node (ref "C22") (pin "P$1") (pinfunction "1_P$1") (pintype "passive"))
      (node (ref "R25") (pin "P$2") (pinfunction "2_P$2") (pintype "passive"))
      (node (ref "U1") (pin "36") (pinfunction "PF7(ADC7(TDI)_36") (pintype "bidirectional"))
    )
    (net (code "10") (name "AD1") (class "Default")
      (node (ref "C23") (pin "P$1") (pinfunction "1_P$1") (pintype "passive"))
      (node (ref "R26") (pin "P$2") (pinfunction "2_P$2") (pintype "passive"))
      (node (ref "U1") (pin "37") (pinfunction "PF6(ADC6/TDO)_37") (pintype "bidirectional"))
    )
    (net (code "11") (name "AD4") (class "Default")
      (node (ref "C24") (pin "P$1") (pinfunction "1_P$1") (pintype "passive"))
      (node (ref "R27") (pin "P$2") (pinfunction "2_P$2") (pintype "passive"))
      (node (ref "U1") (pin "38") (pinfunction "PF5(ADC5/TMS)_38") (pintype "bidirectional"))
    )
    (net (code "12") (name "AD5") (class "Default")
      (node (ref "C25") (pin "P$1") (pinfunction "1_P$1") (pintype "passive"))
      (node (ref "R28") (pin "P$2") (pinfunction "2_P$2") (pintype "passive"))
      (node (ref "U1") (pin "39") (pinfunction "PF4(ADC4/TCK)_39") (pintype "bidirectional"))
    )
    (net (code "13") (name "AD6") (class "Default")
      (node (ref "C26") (pin "P$1") (pinfunction "1_P$1") (pintype "passive"))
      (node (ref "R29") (pin "P$2") (pinfunction "2_P$2") (pintype "passive"))
      (node (ref "U1") (pin "40") (pinfunction "PF1(ADC1)_40") (pintype "bidirectional"))
    )
    (net (code "14") (name "AD7") (class "Default")
      (node (ref "C27") (pin "P$1") (pinfunction "1_P$1") (pintype "passive"))
      (node (ref "R30") (pin "P$2") (pinfunction "2_P$2") (pintype "passive"))
      (node (ref "U1") (pin "41") (pinfunction "PF0(ADC0)_41") (pintype "bidirectional"))
    )
    (net (code "15") (name "BUTTON1") (class "Default")
      (node (ref "C10") (pin "P$1") (pinfunction "1_P$1") (pintype "passive"))
      (node (ref "R8") (pin "P$2") (pinfunction "2_P$2") (pintype "passive"))
      (node (ref "U1") (pin "26") (pinfunction "PD6(T1/ADC9/~{OC4D})_26") (pintype "bidirectional"))
    )
    (net (code "16") (name "BUTTON2") (class "Default")
      (node (ref "C11") (pin "P$1") (pinfunction "1_P$1") (pintype "passive"))
      (node (ref "R9") (pin "P$2") (pinfunction "2_P$2") (pintype "passive"))
      (node (ref "U1") (pin "27") (pinfunction "PD7(OC4D/ADC10/T0)_27") (pintype "bidirectional"))
    )
    (net (code "17") (name "BUTTON3") (class "Default")
      (node (ref "C13") (pin "P$1") (pinfunction "1_P$1") (pintype "passive"))
      (node (ref "R10") (pin "P$2") (pinfunction "2_P$2") (pintype "passive"))
      (node (ref "U1") (pin "28") (pinfunction "PB4(ADC11)_28") (pintype "bidirectional"))
    )
    (net (code "18") (name "BUTTON4") (class "Default")
      (node (ref "C14") (pin "P$1") (pinfunction "1_P$1") (pintype "passive"))
      (node (ref "R11") (pin "P$2") (pinfunction "2_P$2") (pintype "passive"))
    )
    (net (code "19") (name "BUTTON5") (class "Default")
      (node (ref "C15") (pin "P$1") (pinfunction "1_P$1") (pintype "passive"))
      (node (ref "R12") (pin "P$2") (pinfunction "2_P$2") (pintype "passive"))
      (node (ref "U1") (pin "29") (pinfunction "PB5(OC1A/ADC12/~{OC4B})_29") (pintype "bidirectional"))
    )
    (net (code "20") (name "BUTTON6") (class "Default")
      (node (ref "C16") (pin "P$1") (pinfunction "1_P$1") (pintype "passive"))
      (node (ref "R14") (pin "P$2") (pinfunction "2_P$2") (pintype "passive"))
      (node (ref "U1") (pin "30") (pinfunction "PB6(OC1B/OC4B/ADC13)_30") (pintype "bidirectional"))
    )
    (net (code "21") (name "BUTTON7") (class "Default")
      (node (ref "C17") (pin "P$1") (pinfunction "1_P$1") (pintype "passive"))
      (node (ref "R15") (pin "P$2") (pinfunction "2_P$2") (pintype "passive"))
      (node (ref "U1") (pin "12") (pinfunction "PB7(OC0A/OC1C/RTS)_12") (pintype "bidirectional"))
    )
    (net (code "22") (name "BUTTON8") (class "Default")
      (node (ref "C18") (pin "P$1") (pinfunction "1_P$1") (pintype "passive"))
      (node (ref "R19") (pin "P$2") (pinfunction "2_P$2") (pintype "passive"))
      (node (ref "U1") (pin "32") (pinfunction "PC7(ICP3/CLK0/OC4A)_32") (pintype "bidirectional"))
    )
    (net (code "23") (name "CLK_3V3") (class "Default")
      (node (ref "TP1") (pin "P$1") (pinfunction "P$1_P$1") (pintype "bidirectional"))
      (node (ref "U2") (pin "2") (pinfunction "SCK_2") (pintype "bidirectional"))
      (node (ref "U4") (pin "7") (pinfunction "B1_7") (pintype "bidirectional"))
      (node (ref "X11") (pin "5") (pinfunction "CLK_5") (pintype "bidirectional"))
    )
    (net (code "24") (name "CLK_5V") (class "Default")
      (node (ref "TP15") (pin "P$1") (pinfunction "P$1_P$1") (pintype "bidirectional"))
      (node (ref "TP2") (pin "P$1") (pinfunction "P$1_P$1") (pintype "bidirectional"))
      (node (ref "U1") (pin "9") (pinfunction "PB1(SCK)_9") (pintype "bidirectional"))
      (node (ref "U4") (pin "2") (pinfunction "A1_2") (pintype "bidirectional"))
      (node (ref "X2") (pin "3") (pinfunction "SCK_3") (pintype "output"))
    )
    (net (code "25") (name "GND") (class "Default")
      (node (ref "C1") (pin "P$2") (pinfunction "2_P$2") (pintype "passive"))
      (node (ref "C10") (pin "P$2") (pinfunction "2_P$2") (pintype "passive"))
      (node (ref "C11") (pin "P$2") (pinfunction "2_P$2") (pintype "passive"))
      (node (ref "C12") (pin "P$2") (pinfunction "2_P$2") (pintype "passive"))
      (node (ref "C13") (pin "P$2") (pinfunction "2_P$2") (pintype "passive"))
      (node (ref "C14") (pin "P$2") (pinfunction "2_P$2") (pintype "passive"))
      (node (ref "C15") (pin "P$2") (pinfunction "2_P$2") (pintype "passive"))
      (node (ref "C16") (pin "P$2") (pinfunction "2_P$2") (pintype "passive"))
      (node (ref "C17") (pin "P$2") (pinfunction "2_P$2") (pintype "passive"))
      (node (ref "C18") (pin "P$2") (pinfunction "2_P$2") (pintype "passive"))
      (node (ref "C19") (pin "P$1") (pinfunction "1_P$1") (pintype "passive"))
      (node (ref "C2") (pin "P$2") (pinfunction "2_P$2") (pintype "passive"))
      (node (ref "C20") (pin "P$1") (pinfunction "1_P$1") (pintype "passive"))
      (node (ref "C21") (pin "P$1") (pinfunction "1_P$1") (pintype "passive"))
      (node (ref "C22") (pin "P$2") (pinfunction "2_P$2") (pintype "passive"))
      (node (ref "C23") (pin "P$2") (pinfunction "2_P$2") (pintype "passive"))
      (node (ref "C24") (pin "P$2") (pinfunction "2_P$2") (pintype "passive"))
      (node (ref "C25") (pin "P$2") (pinfunction "2_P$2") (pintype "passive"))
      (node (ref "C26") (pin "P$2") (pinfunction "2_P$2") (pintype "passive"))
      (node (ref "C27") (pin "P$2") (pinfunction "2_P$2") (pintype "passive"))
      (node (ref "C28") (pin "P$2") (pinfunction "2_P$2") (pintype "passive"))
      (node (ref "C29") (pin "P$2") (pinfunction "2_P$2") (pintype "passive"))
      (node (ref "C3") (pin "P$2") (pinfunction "2_P$2") (pintype "passive"))
      (node (ref "C30") (pin "P$1") (pinfunction "1_P$1") (pintype "passive"))
      (node (ref "C31") (pin "P$2") (pinfunction "2_P$2") (pintype "passive"))
      (node (ref "C32") (pin "P$2") (pinfunction "2_P$2") (pintype "passive"))
      (node (ref "C33") (pin "P$1") (pinfunction "1_P$1") (pintype "passive"))
      (node (ref "C34") (pin "P$2") (pinfunction "2_P$2") (pintype "passive"))
      (node (ref "C4") (pin "P$2") (pinfunction "2_P$2") (pintype "passive"))
      (node (ref "C44") (pin "P$2") (pinfunction "2_P$2") (pintype "passive"))
      (node (ref "C46") (pin "P$1") (pinfunction "1_P$1") (pintype "passive"))
      (node (ref "C48") (pin "P$2") (pinfunction "2_P$2") (pintype "passive"))
      (node (ref "C5") (pin "P$2") (pinfunction "2_P$2") (pintype "passive"))
      (node (ref "C6") (pin "P$2") (pinfunction "2_P$2") (pintype "passive"))
      (node (ref "C7") (pin "P$2") (pinfunction "2_P$2") (pintype "passive"))
      (node (ref "C9") (pin "P$1") (pinfunction "1_P$1") (pintype "passive"))
      (node (ref "D2") (pin "A") (pinfunction "A_A") (pintype "passive"))
      (node (ref "D27") (pin "C") (pinfunction "CATHODE_C") (pintype "passive"))
      (node (ref "D3") (pin "C") (pinfunction "CATHODE_C") (pintype "passive"))
      (node (ref "D4") (pin "C") (pinfunction "CATHODE_C") (pintype "passive"))
      (node (ref "FB2") (pin "P$1") (pinfunction "1_P$1") (pintype "passive"))
      (node (ref "FB4") (pin "P$1") (pinfunction "1_P$1") (pintype "passive"))
      (node (ref "R24") (pin "P$2") (pinfunction "2_P$2") (pintype "passive"))
      (node (ref "R7") (pin "P$2") (pinfunction "2_P$2") (pintype "passive"))
      (node (ref "S1") (pin "1") (pinfunction "P$1_1") (pintype "bidirectional"))
      (node (ref "S10") (pin "3") (pinfunction "P$2_3") (pintype "bidirectional"))
      (node (ref "S3") (pin "1") (pinfunction "P$1_1") (pintype "bidirectional"))
      (node (ref "S4") (pin "1") (pinfunction "P$1_1") (pintype "bidirectional"))
      (node (ref "S5") (pin "1") (pinfunction "P$1_1") (pintype "bidirectional"))
      (node (ref "S6") (pin "1") (pinfunction "P$1_1") (pintype "bidirectional"))
      (node (ref "S7") (pin "1") (pinfunction "P$1_1") (pintype "bidirectional"))
      (node (ref "S8") (pin "1") (pinfunction "P$1_1") (pintype "bidirectional"))
      (node (ref "S9") (pin "1") (pinfunction "P$1_1") (pintype "bidirectional"))
      (node (ref "U1") (pin "15") (pinfunction "GND_15") (pintype "bidirectional"))
      (node (ref "U1") (pin "23") (pinfunction "GND1_23") (pintype "bidirectional"))
      (node (ref "U1") (pin "35") (pinfunction "GND2_35") (pintype "bidirectional"))
      (node (ref "U1") (pin "43") (pinfunction "GND3_43") (pintype "bidirectional"))
      (node (ref "U2") (pin "7") (pinfunction "GND_7") (pintype "bidirectional"))
      (node (ref "U3") (pin "1") (pinfunction "GND_1") (pintype "passive"))
      (node (ref "U4") (pin "4") (pinfunction "GND_4") (pintype "power_in"))
      (node (ref "U5") (pin "4") (pinfunction "GND_4") (pintype "power_in"))
      (node (ref "U5") (pin "5") (pinfunction "DIR_5") (pintype "input"))
      (node (ref "U6") (pin "4") (pinfunction "GND_4") (pintype "power_in"))
      (node (ref "X11") (pin "6") (pinfunction "VSS_6") (pintype "bidirectional"))
      (node (ref "X11") (pin "DET_LVR") (pinfunction "LAT_DET_LVR") (pintype "bidirectional"))
      (node (ref "X13") (pin "P$1") (pinfunction "P$1_P$1") (pintype "bidirectional"))
      (node (ref "X13") (pin "P$2") (pinfunction "P$2_P$2") (pintype "bidirectional"))
      (node (ref "X14") (pin "4") (pinfunction "4_4") (pintype "passive"))
      (node (ref "X15") (pin "8") (pinfunction "8_8") (pintype "passive"))
      (node (ref "X2") (pin "6") (pinfunction "GND_6") (pintype "input"))
      (node (ref "X3") (pin "4") (pinfunction "4_4") (pintype "passive"))
    )
    (net (code "26") (name "GND_E") (class "Default")
      (node (ref "FB2") (pin "P$2") (pinfunction "2_P$2") (pintype "passive"))
      (node (ref "X1") (pin "G1") (pinfunction "TAB_G1") (pintype "bidirectional"))
      (node (ref "X1") (pin "G2") (pinfunction "TAB_G2") (pintype "bidirectional"))
      (node (ref "X1") (pin "H1") (pinfunction "TAB_H1") (pintype "bidirectional"))
      (node (ref "X1") (pin "H2") (pinfunction "TAB_H2") (pintype "bidirectional"))
      (node (ref "X1") (pin "H3") (pinfunction "TAB_H3") (pintype "bidirectional"))
      (node (ref "X1") (pin "H4") (pinfunction "TAB_H4") (pintype "bidirectional"))
      (node (ref "X11") (pin "H1") (pinfunction "GND1_H1") (pintype "bidirectional"))
      (node (ref "X11") (pin "H2") (pinfunction "GND2_H2") (pintype "bidirectional"))
      (node (ref "X11") (pin "H3") (pinfunction "GND3_H3") (pintype "bidirectional"))
      (node (ref "X11") (pin "H4") (pinfunction "GND4_H4") (pintype "bidirectional"))
    )
    (net (code "27") (name "INTERRUPT7") (class "Default")
      (node (ref "R31") (pin "P$2") (pinfunction "2_P$2") (pintype "passive"))
      (node (ref "U1") (pin "1") (pinfunction "PE6(INT.6/AIN0)_1") (pintype "bidirectional"))
    )
    (net (code "28") (name "MISO_3V3") (class "Default")
      (node (ref "U2") (pin "8") (pinfunction "MISO_8") (pintype "bidirectional"))
      (node (ref "U5") (pin "7") (pinfunction "B1_7") (pintype "bidirectional"))
      (node (ref "X11") (pin "7") (pinfunction "DAT0_7") (pintype "bidirectional"))
    )
    (net (code "29") (name "MISO_5V") (class "Default")
      (node (ref "TP16") (pin "P$1") (pinfunction "P$1_P$1") (pintype "bidirectional"))
      (node (ref "U1") (pin "11") (pinfunction "PB3(PDO/MISO)_11") (pintype "bidirectional"))
      (node (ref "U5") (pin "2") (pinfunction "A1_2") (pintype "bidirectional"))
      (node (ref "X2") (pin "1") (pinfunction "MISO_1") (pintype "input"))
    )
    (net (code "30") (name "MOSI_3V3") (class "Default")
      (node (ref "U2") (pin "1") (pinfunction "MOSI_1") (pintype "bidirectional"))
      (node (ref "U4") (pin "6") (pinfunction "B2_6") (pintype "bidirectional"))
      (node (ref "X11") (pin "3") (pinfunction "CMD_3") (pintype "bidirectional"))
    )
    (net (code "31") (name "MOSI_5V") (class "Default")
      (node (ref "TP17") (pin "P$1") (pinfunction "P$1_P$1") (pintype "bidirectional"))
      (node (ref "U1") (pin "10") (pinfunction "PB2(PDI/MOSI)_10") (pintype "bidirectional"))
      (node (ref "U4") (pin "3") (pinfunction "A2_3") (pintype "bidirectional"))
      (node (ref "X2") (pin "4") (pinfunction "MOSI_4") (pintype "output"))
    )
    (net (code "32") (name "Net-(C1-1)") (class "Default")
      (node (ref "C1") (pin "P$1") (pinfunction "1_P$1") (pintype "passive"))
      (node (ref "R6") (pin "P$1") (pinfunction "1_P$1") (pintype "passive"))
      (node (ref "U1") (pin "17") (pinfunction "XTAL1_17") (pintype "bidirectional"))
      (node (ref "Y1") (pin "2") (pinfunction "2_2") (pintype "passive"))
    )
    (net (code "33") (name "Net-(C2-1)") (class "Default")
      (node (ref "C2") (pin "P$1") (pinfunction "1_P$1") (pintype "passive"))
      (node (ref "R6") (pin "P$2") (pinfunction "2_P$2") (pintype "passive"))
      (node (ref "U1") (pin "16") (pinfunction "XTAL2_16") (pintype "bidirectional"))
      (node (ref "Y1") (pin "1") (pinfunction "1_1") (pintype "passive"))
    )
    (net (code "34") (name "Net-(C7-1)") (class "Default")
      (node (ref "C7") (pin "P$1") (pinfunction "1_P$1") (pintype "passive"))
      (node (ref "FB3") (pin "P$2") (pinfunction "2_P$2") (pintype "passive"))
      (node (ref "U1") (pin "24") (pinfunction "AVCC_24") (pintype "bidirectional"))
      (node (ref "U1") (pin "44") (pinfunction "AVCC1_44") (pintype "bidirectional"))
    )
    (net (code "35") (name "Net-(C8-2)") (class "Default")
      (node (ref "C8") (pin "P$2") (pinfunction "2_P$2") (pintype "passive"))
      (node (ref "U1") (pin "6") (pinfunction "UCAP_6") (pintype "bidirectional"))
    )
    (net (code "36") (name "Net-(D1-Pad1)") (class "Default")
      (node (ref "D1") (pin "1") (pinfunction "1_1") (pintype "bidirectional"))
      (node (ref "L1") (pin "A2") (pinfunction "A2_A2") (pintype "bidirectional"))
      (node (ref "X1") (pin "D+") (pinfunction "D+_D+") (pintype "bidirectional"))
    )
    (net (code "37") (name "Net-(D1-Pad6)") (class "Default")
      (node (ref "D1") (pin "6") (pinfunction "6_6") (pintype "bidirectional"))
      (node (ref "L1") (pin "B2") (pinfunction "B2_B2") (pintype "bidirectional"))
      (node (ref "X1") (pin "D-") (pinfunction "D-_D-") (pintype "bidirectional"))
    )
    (net (code "38") (name "Net-(D3-ANODE)") (class "Default")
      (node (ref "D3") (pin "A") (pinfunction "ANODE_A") (pintype "passive"))
      (node (ref "R23") (pin "P$1") (pinfunction "1_P$1") (pintype "passive"))
    )
    (net (code "39") (name "Net-(D4-ANODE)") (class "Default")
      (node (ref "D4") (pin "A") (pinfunction "ANODE_A") (pintype "passive"))
      (node (ref "R18") (pin "P$1") (pinfunction "1_P$1") (pintype "passive"))
    )
    (net (code "40") (name "Net-(D27-ANODE)") (class "Default")
      (node (ref "D27") (pin "A") (pinfunction "ANODE_A") (pintype "passive"))
      (node (ref "R13") (pin "P$1") (pinfunction "1_P$1") (pintype "passive"))
    )
    (net (code "41") (name "Net-(FB6-1)") (class "Default")
      (node (ref "FB6") (pin "P$1") (pinfunction "1_P$1") (pintype "passive"))
      (node (ref "X15") (pin "1") (pinfunction "1_1") (pintype "passive"))
    )
    (net (code "42") (name "Net-(R2-2)") (class "Default")
      (node (ref "R2") (pin "P$2") (pinfunction "2_P$2") (pintype "passive"))
      (node (ref "X3") (pin "2") (pinfunction "2_2") (pintype "passive"))
    )
    (net (code "43") (name "Net-(R3-2)") (class "Default")
      (node (ref "R3") (pin "P$2") (pinfunction "2_P$2") (pintype "passive"))
      (node (ref "X3") (pin "3") (pinfunction "3_3") (pintype "passive"))
    )
    (net (code "44") (name "Net-(R4-1)") (class "Default")
      (node (ref "L1") (pin "A1") (pinfunction "A1_A1") (pintype "bidirectional"))
      (node (ref "R4") (pin "P$1") (pinfunction "1_P$1") (pintype "passive"))
    )
    (net (code "45") (name "Net-(R5-1)") (class "Default")
      (node (ref "L1") (pin "B1") (pinfunction "B1_B1") (pintype "bidirectional"))
      (node (ref "R5") (pin "P$1") (pinfunction "1_P$1") (pintype "passive"))
    )
    (net (code "46") (name "Net-(R7-1)") (class "Default")
      (node (ref "R7") (pin "P$1") (pinfunction "1_P$1") (pintype "passive"))
      (node (ref "U1") (pin "33") (pinfunction "PE2(~{HWB})_33") (pintype "bidirectional"))
    )
    (net (code "47") (name "Net-(R8-1)") (class "Default")
      (node (ref "R8") (pin "P$1") (pinfunction "1_P$1") (pintype "passive"))
      (node (ref "S1") (pin "2") (pinfunction "P$2_2") (pintype "bidirectional"))
    )
    (net (code "48") (name "Net-(R9-1)") (class "Default")
      (node (ref "R9") (pin "P$1") (pinfunction "1_P$1") (pintype "passive"))
      (node (ref "S3") (pin "2") (pinfunction "P$2_2") (pintype "bidirectional"))
    )
    (net (code "49") (name "Net-(R10-1)") (class "Default")
      (node (ref "R10") (pin "P$1") (pinfunction "1_P$1") (pintype "passive"))
      (node (ref "S4") (pin "2") (pinfunction "P$2_2") (pintype "bidirectional"))
    )
    (net (code "50") (name "Net-(R11-1)") (class "Default")
      (node (ref "R11") (pin "P$1") (pinfunction "1_P$1") (pintype "passive"))
      (node (ref "S5") (pin "2") (pinfunction "P$2_2") (pintype "bidirectional"))
    )
    (net (code "51") (name "Net-(R12-1)") (class "Default")
      (node (ref "R12") (pin "P$1") (pinfunction "1_P$1") (pintype "passive"))
      (node (ref "S6") (pin "2") (pinfunction "P$2_2") (pintype "bidirectional"))
    )
    (net (code "52") (name "Net-(R14-1)") (class "Default")
      (node (ref "R14") (pin "P$1") (pinfunction "1_P$1") (pintype "passive"))
      (node (ref "S7") (pin "2") (pinfunction "P$2_2") (pintype "bidirectional"))
    )
    (net (code "53") (name "Net-(R15-1)") (class "Default")
      (node (ref "R15") (pin "P$1") (pinfunction "1_P$1") (pintype "passive"))
      (node (ref "S8") (pin "2") (pinfunction "P$2_2") (pintype "bidirectional"))
    )
    (net (code "54") (name "Net-(R16-1)") (class "Default")
      (node (ref "R16") (pin "P$1") (pinfunction "1_P$1") (pintype "passive"))
      (node (ref "X2") (pin "2") (pinfunction "VCC_2") (pintype "input"))
    )
    (net (code "55") (name "Net-(R17-1)") (class "Default")
      (node (ref "R17") (pin "P$1") (pinfunction "1_P$1") (pintype "passive"))
      (node (ref "R21") (pin "P$1") (pinfunction "1_P$1") (pintype "passive"))
      (node (ref "X14") (pin "1") (pinfunction "1_1") (pintype "passive"))
    )
    (net (code "56") (name "Net-(R19-1)") (class "Default")
      (node (ref "R19") (pin "P$1") (pinfunction "1_P$1") (pintype "passive"))
      (node (ref "S9") (pin "2") (pinfunction "P$2_2") (pintype "bidirectional"))
    )
    (net (code "57") (name "Net-(R20-1)") (class "Default")
      (node (ref "R20") (pin "P$1") (pinfunction "1_P$1") (pintype "passive"))
      (node (ref "R22") (pin "P$1") (pinfunction "1_P$1") (pintype "passive"))
      (node (ref "X14") (pin "2") (pinfunction "2_2") (pintype "passive"))
    )
    (net (code "58") (name "Net-(R24-1)") (class "Default")
      (node (ref "R24") (pin "P$1") (pinfunction "1_P$1") (pintype "passive"))
      (node (ref "U5") (pin "6") (pinfunction "B2_6") (pintype "bidirectional"))
    )
    (net (code "59") (name "Net-(R25-1)") (class "Default")
      (node (ref "R25") (pin "P$1") (pinfunction "1_P$1") (pintype "passive"))
      (node (ref "X15") (pin "2") (pinfunction "2_2") (pintype "passive"))
    )
    (net (code "60") (name "Net-(R26-1)") (class "Default")
      (node (ref "R26") (pin "P$1") (pinfunction "1_P$1") (pintype "passive"))
      (node (ref "X15") (pin "3") (pinfunction "3_3") (pintype "passive"))
    )
    (net (code "61") (name "Net-(R27-1)") (class "Default")
      (node (ref "R27") (pin "P$1") (pinfunction "1_P$1") (pintype "passive"))
      (node (ref "X15") (pin "4") (pinfunction "4_4") (pintype "passive"))
    )
    (net (code "62") (name "Net-(R28-1)") (class "Default")
      (node (ref "R28") (pin "P$1") (pinfunction "1_P$1") (pintype "passive"))
      (node (ref "X15") (pin "5") (pinfunction "5_5") (pintype "passive"))
    )
    (net (code "63") (name "Net-(R29-1)") (class "Default")
      (node (ref "R29") (pin "P$1") (pinfunction "1_P$1") (pintype "passive"))
      (node (ref "X15") (pin "6") (pinfunction "6_6") (pintype "passive"))
    )
    (net (code "64") (name "Net-(R30-1)") (class "Default")
      (node (ref "R30") (pin "P$1") (pinfunction "1_P$1") (pintype "passive"))
      (node (ref "X15") (pin "7") (pinfunction "7_7") (pintype "passive"))
    )
    (net (code "65") (name "Net-(R31-1)") (class "Default")
      (node (ref "R31") (pin "P$1") (pinfunction "1_P$1") (pintype "passive"))
      (node (ref "X14") (pin "3") (pinfunction "3_3") (pintype "passive"))
    )
    (net (code "66") (name "Net-(R33-1)") (class "Default")
      (node (ref "R33") (pin "P$1") (pinfunction "1_P$1") (pintype "passive"))
      (node (ref "U2") (pin "5") (pinfunction "~{WP}_5") (pintype "bidirectional"))
    )
    (net (code "67") (name "RXD") (class "Default")
      (node (ref "R2") (pin "P$1") (pinfunction "1_P$1") (pintype "passive"))
      (node (ref "U1") (pin "20") (pinfunction "PD2(INT2/RXD1)_20") (pintype "bidirectional"))
    )
    (net (code "68") (name "RX_LED") (class "Default")
      (node (ref "R13") (pin "P$2") (pinfunction "2_P$2") (pintype "passive"))
      (node (ref "U1") (pin "8") (pinfunction "PB0(SS)_8") (pintype "bidirectional"))
    )
    (net (code "69") (name "SCL_5V") (class "Default")
      (node (ref "R21") (pin "P$2") (pinfunction "2_P$2") (pintype "passive"))
      (node (ref "U1") (pin "18") (pinfunction "PD0(INT0/OC0B/SCL)_18") (pintype "bidirectional"))
    )
    (net (code "70") (name "SDA_5V") (class "Default")
      (node (ref "R22") (pin "P$2") (pinfunction "2_P$2") (pintype "passive"))
      (node (ref "U1") (pin "19") (pinfunction "PD1(INT1/SDA)_19") (pintype "bidirectional"))
    )
    (net (code "71") (name "SD_DETECT") (class "Default")
      (node (ref "X11") (pin "DET_SW") (pinfunction "SW_DET_SW") (pintype "bidirectional"))
    )
    (net (code "72") (name "TXD") (class "Default")
      (node (ref "R3") (pin "P$1") (pinfunction "1_P$1") (pintype "passive"))
      (node (ref "U1") (pin "21") (pinfunction "PD3(INT3/TXD1)_21") (pintype "bidirectional"))
    )
    (net (code "73") (name "TX_LED") (class "Default")
      (node (ref "R18") (pin "P$2") (pinfunction "2_P$2") (pintype "passive"))
      (node (ref "U1") (pin "22") (pinfunction "PD5(XCK/CTS)_22") (pintype "bidirectional"))
    )
    (net (code "74") (name "USB_D+") (class "Default")
      (node (ref "R4") (pin "P$2") (pinfunction "2_P$2") (pintype "passive"))
      (node (ref "U1") (pin "4") (pinfunction "D+_4") (pintype "bidirectional"))
    )
    (net (code "75") (name "USB_D-") (class "Default")
      (node (ref "R5") (pin "P$2") (pinfunction "2_P$2") (pintype "passive"))
      (node (ref "U1") (pin "3") (pinfunction "D-_3") (pintype "bidirectional"))
    )
    (net (code "76") (name "USB_GND") (class "Default")
      (node (ref "C8") (pin "P$1") (pinfunction "1_P$1") (pintype "passive"))
      (node (ref "D1") (pin "2") (pinfunction "V-_2") (pintype "bidirectional"))
      (node (ref "FB4") (pin "P$2") (pinfunction "2_P$2") (pintype "passive"))
      (node (ref "U1") (pin "5") (pinfunction "UGND_5") (pintype "bidirectional"))
      (node (ref "X1") (pin "GND") (pinfunction "GND_GND") (pintype "bidirectional"))
    )
    (net (code "77") (name "USB_ID") (class "Default")
      (node (ref "X1") (pin "ID") (pinfunction "ID_ID") (pintype "bidirectional"))
    )
    (net (code "78") (name "USB_VBUS") (class "Default")
      (node (ref "FB1") (pin "P$1") (pinfunction "1_P$1") (pintype "passive"))
      (node (ref "U1") (pin "7") (pinfunction "VBUS_7") (pintype "bidirectional"))
      (node (ref "X1") (pin "VBUS") (pinfunction "V+_VBUS") (pintype "bidirectional"))
    )
    (net (code "79") (name "unconnected-(D1-Pad3)") (class "Default")
      (node (ref "D1") (pin "3") (pinfunction "3_3") (pintype "bidirectional"))
    )
    (net (code "80") (name "unconnected-(D1-Pad4)") (class "Default")
      (node (ref "D1") (pin "4") (pinfunction "4_4") (pintype "bidirectional"))
    )
    (net (code "81") (name "unconnected-(U1-AREF-Pad42)") (class "Default")
      (node (ref "U1") (pin "42") (pinfunction "AREF_42") (pintype "bidirectional"))
    )
    (net (code "82") (name "unconnected-(U5-A2-Pad3)") (class "Default")
      (node (ref "U5") (pin "3") (pinfunction "A2_3") (pintype "bidirectional"))
    )
    (net (code "83") (name "unconnected-(X11-DAT1-Pad8)") (class "Default")
      (node (ref "X11") (pin "8") (pinfunction "DAT1_8") (pintype "bidirectional"))
    )
    (net (code "84") (name "unconnected-(X11-DAT2-Pad1)") (class "Default")
      (node (ref "X11") (pin "1") (pinfunction "DAT2_1") (pintype "bidirectional"))
    )
  )
)
